# HSI-interface-2.net
KiCad netlist of a schematic drawn in EAGLE
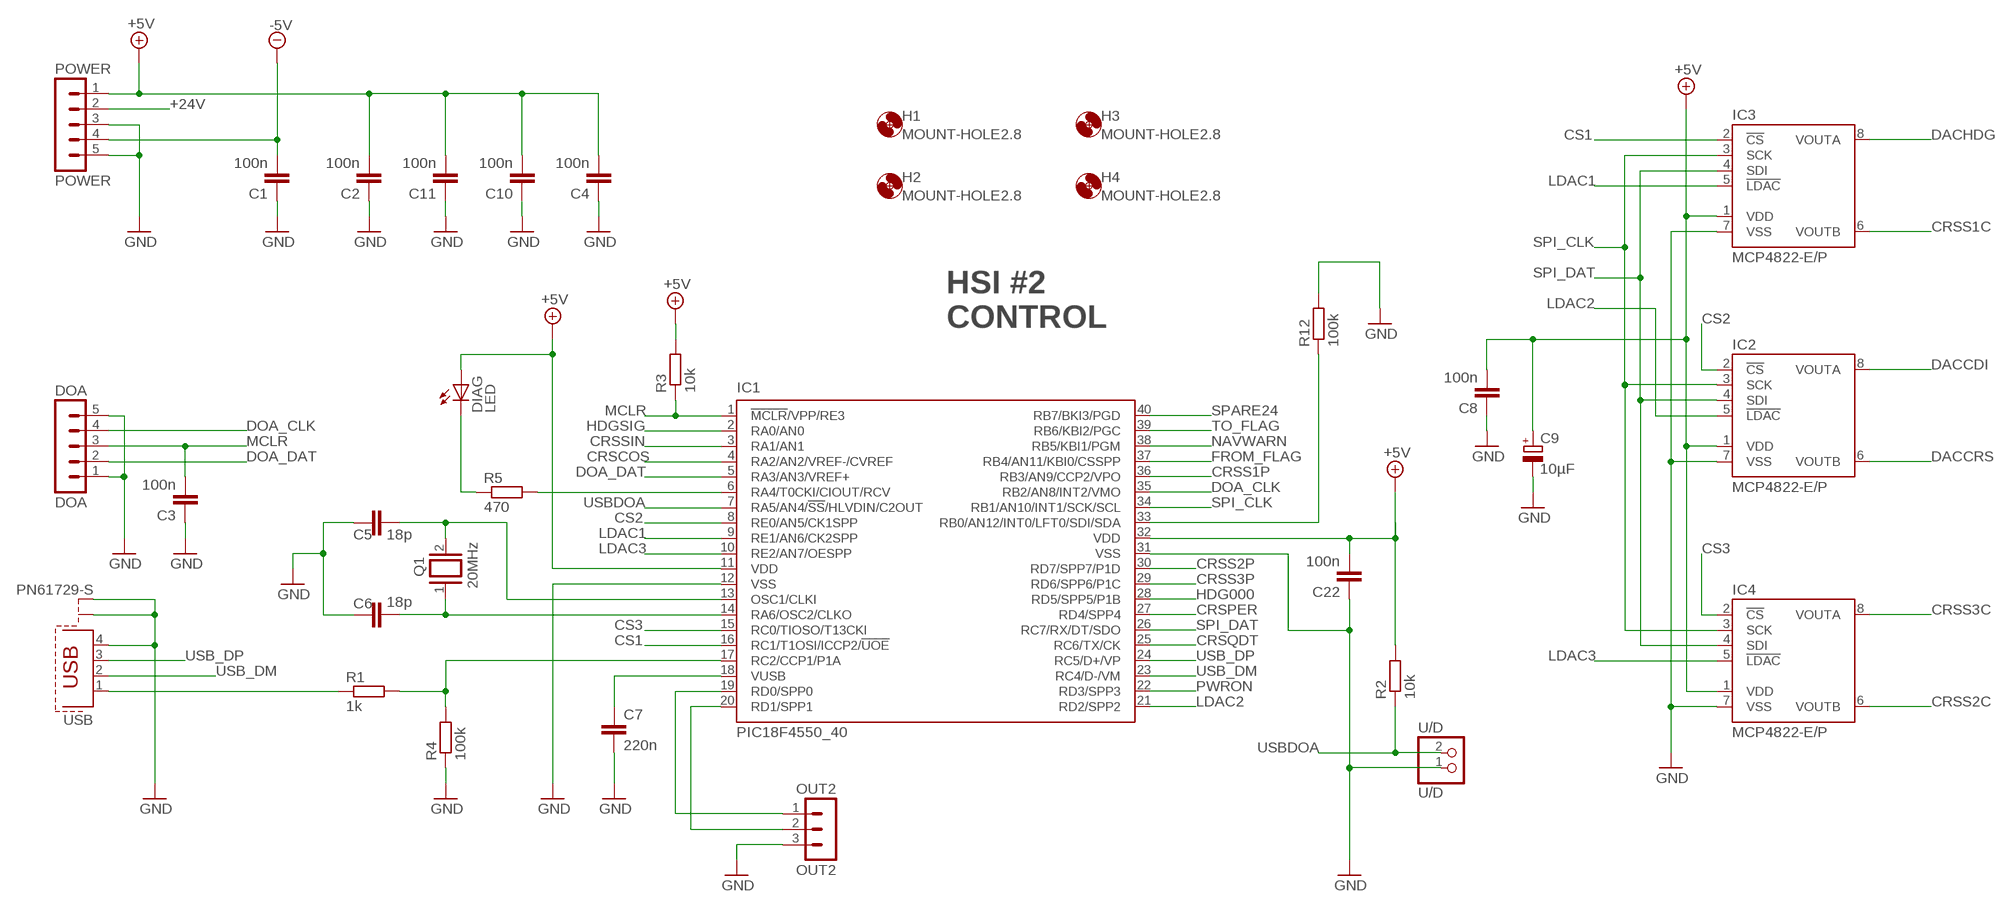
[diagram p0: schematic, sheet 1]
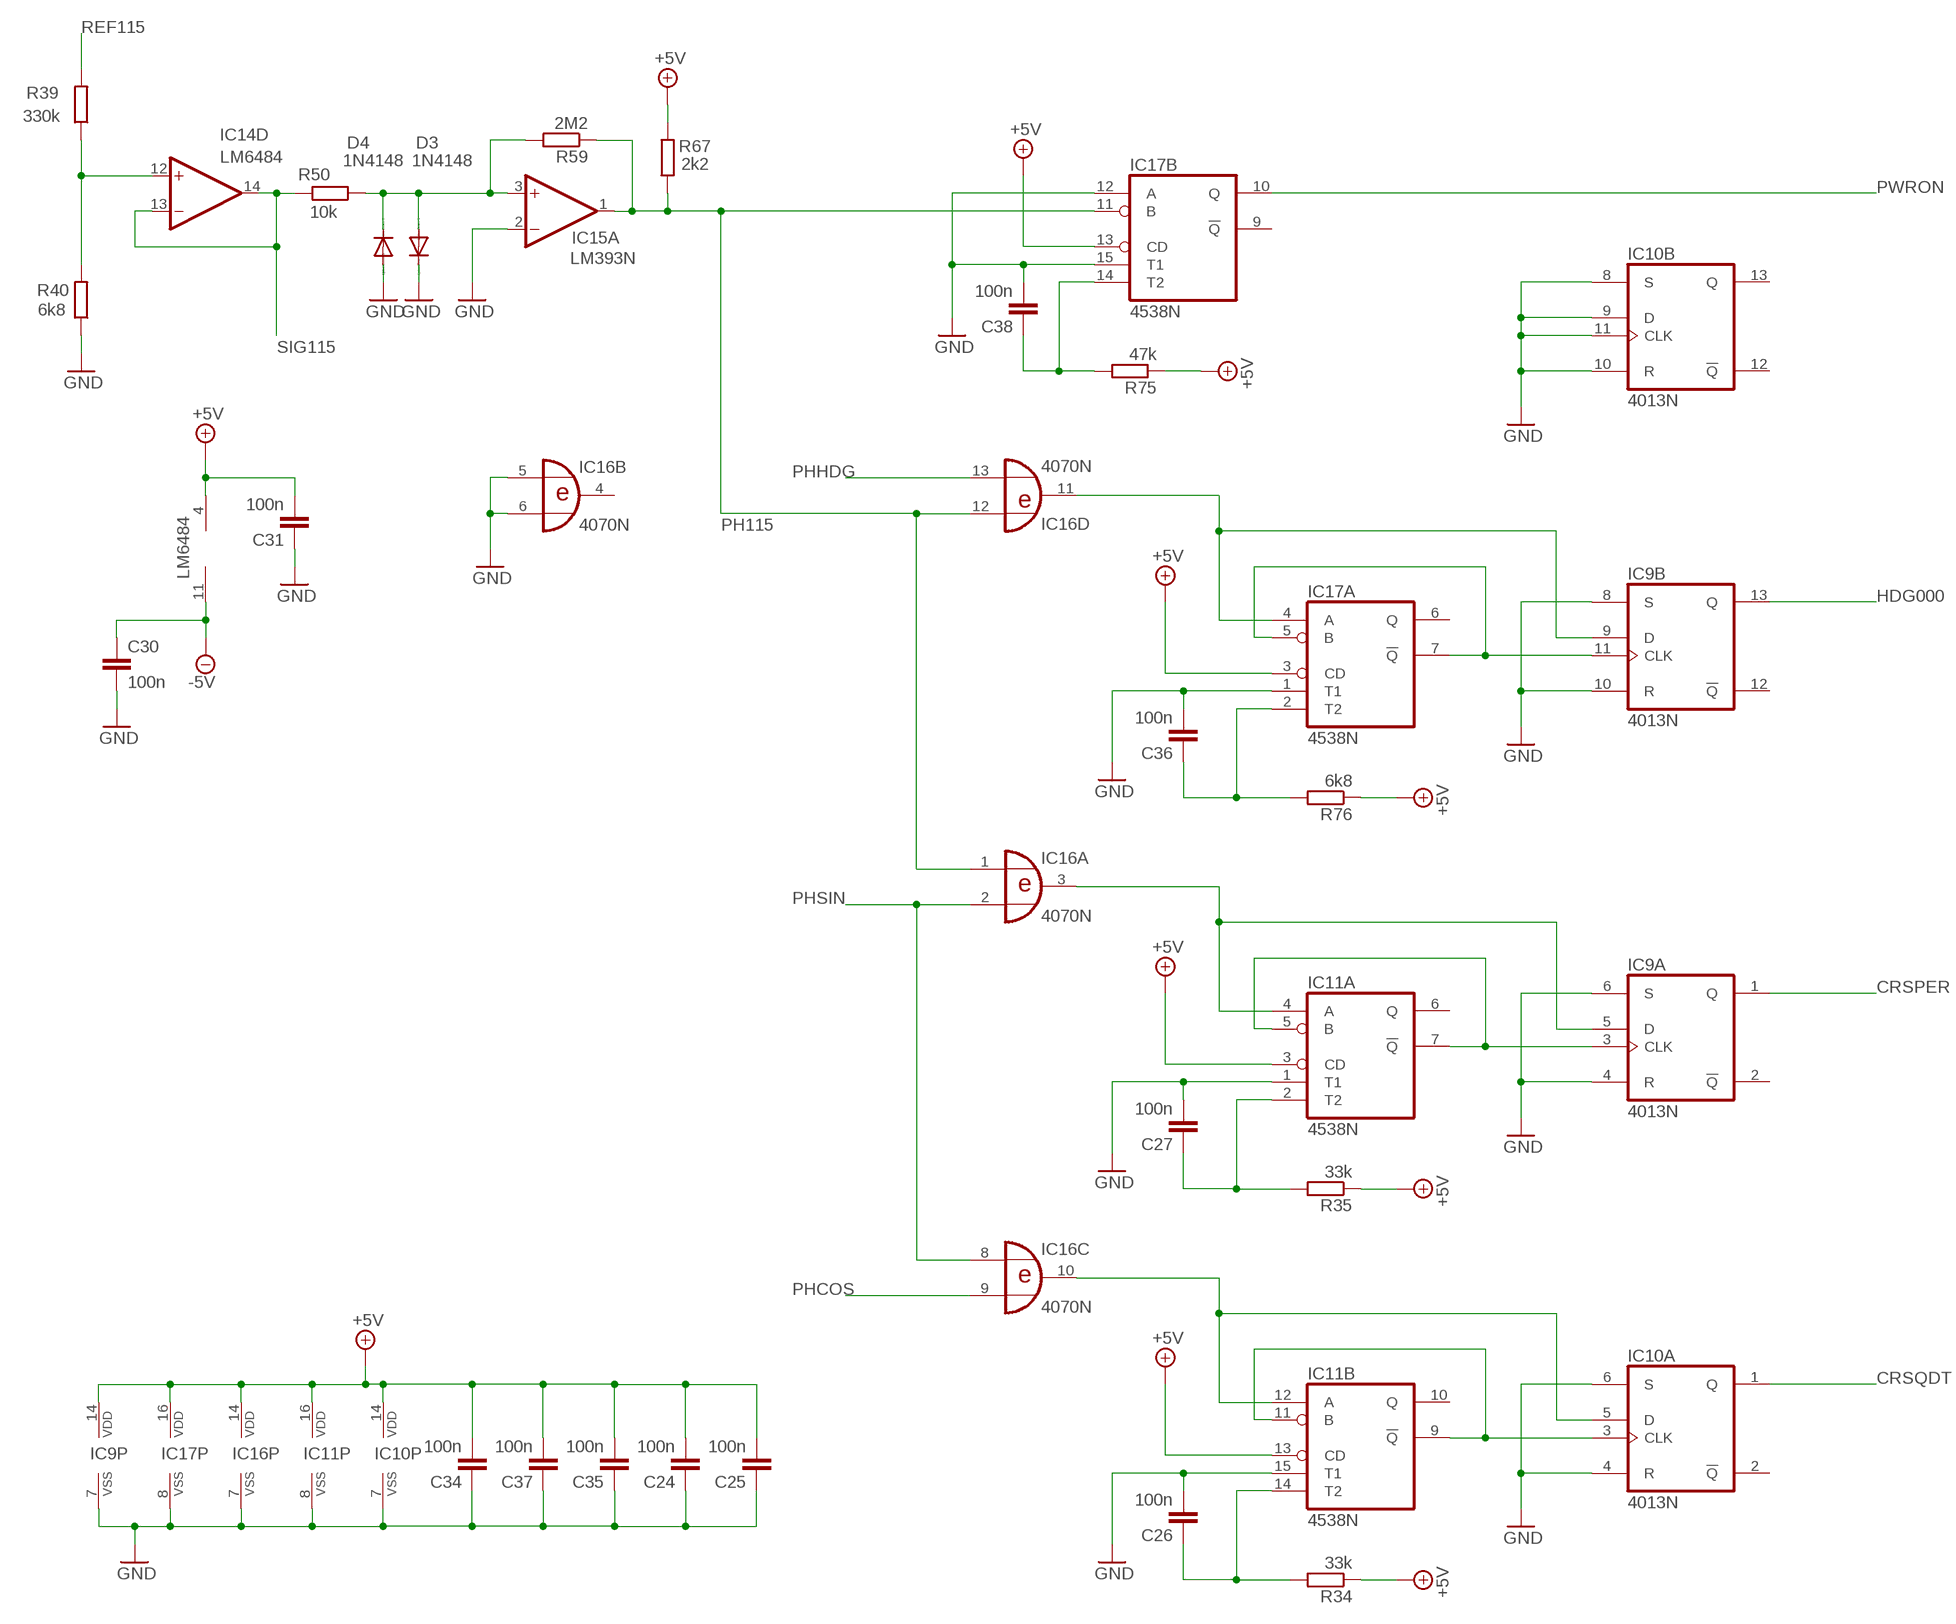
[diagram p1: schematic, sheet 2]
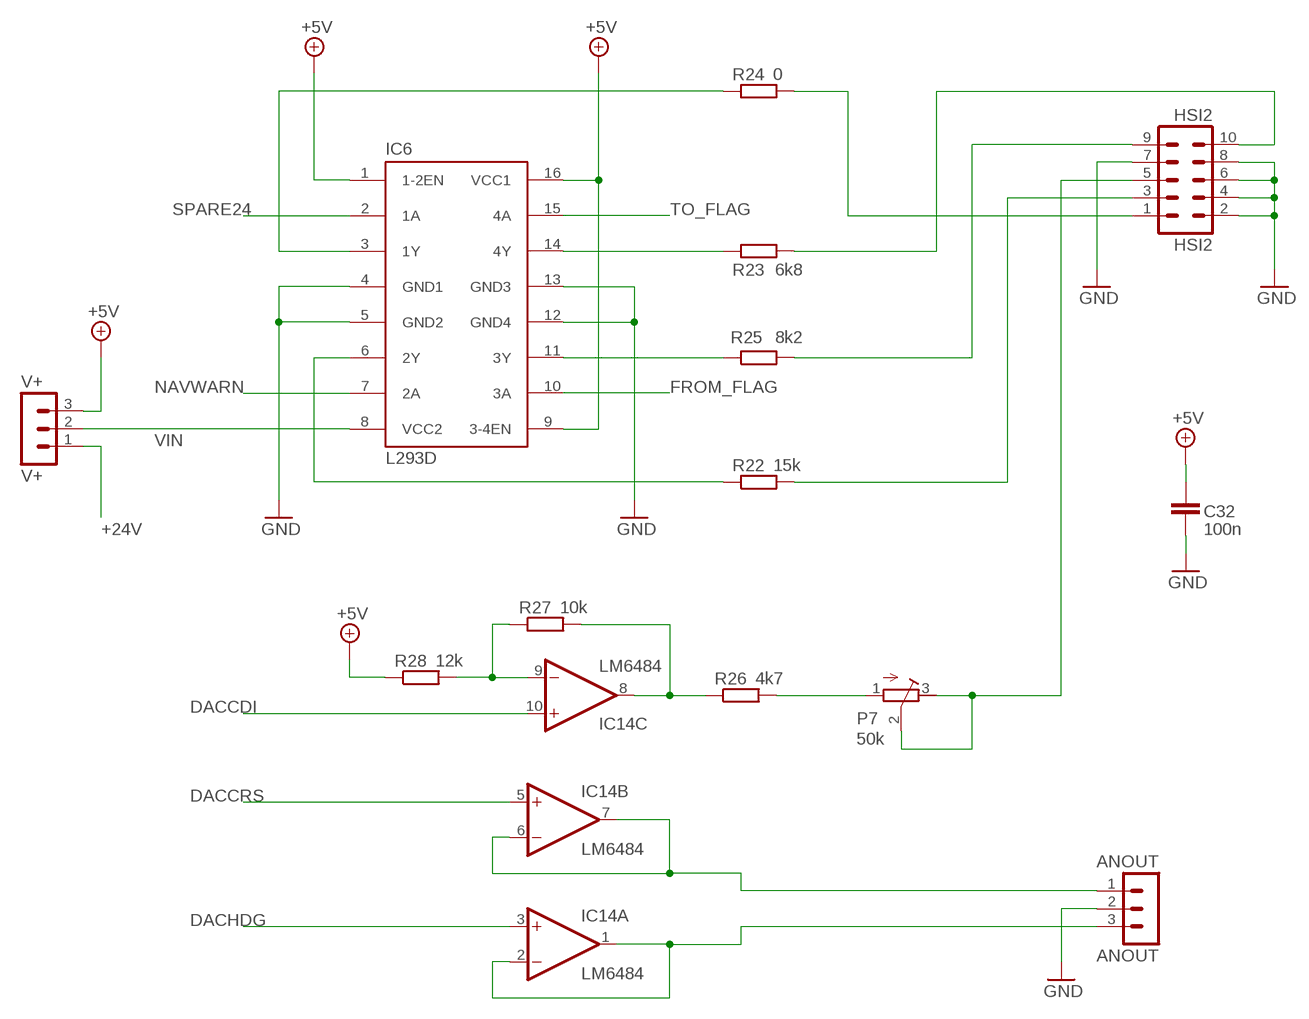
[diagram p2: schematic, sheet 3]
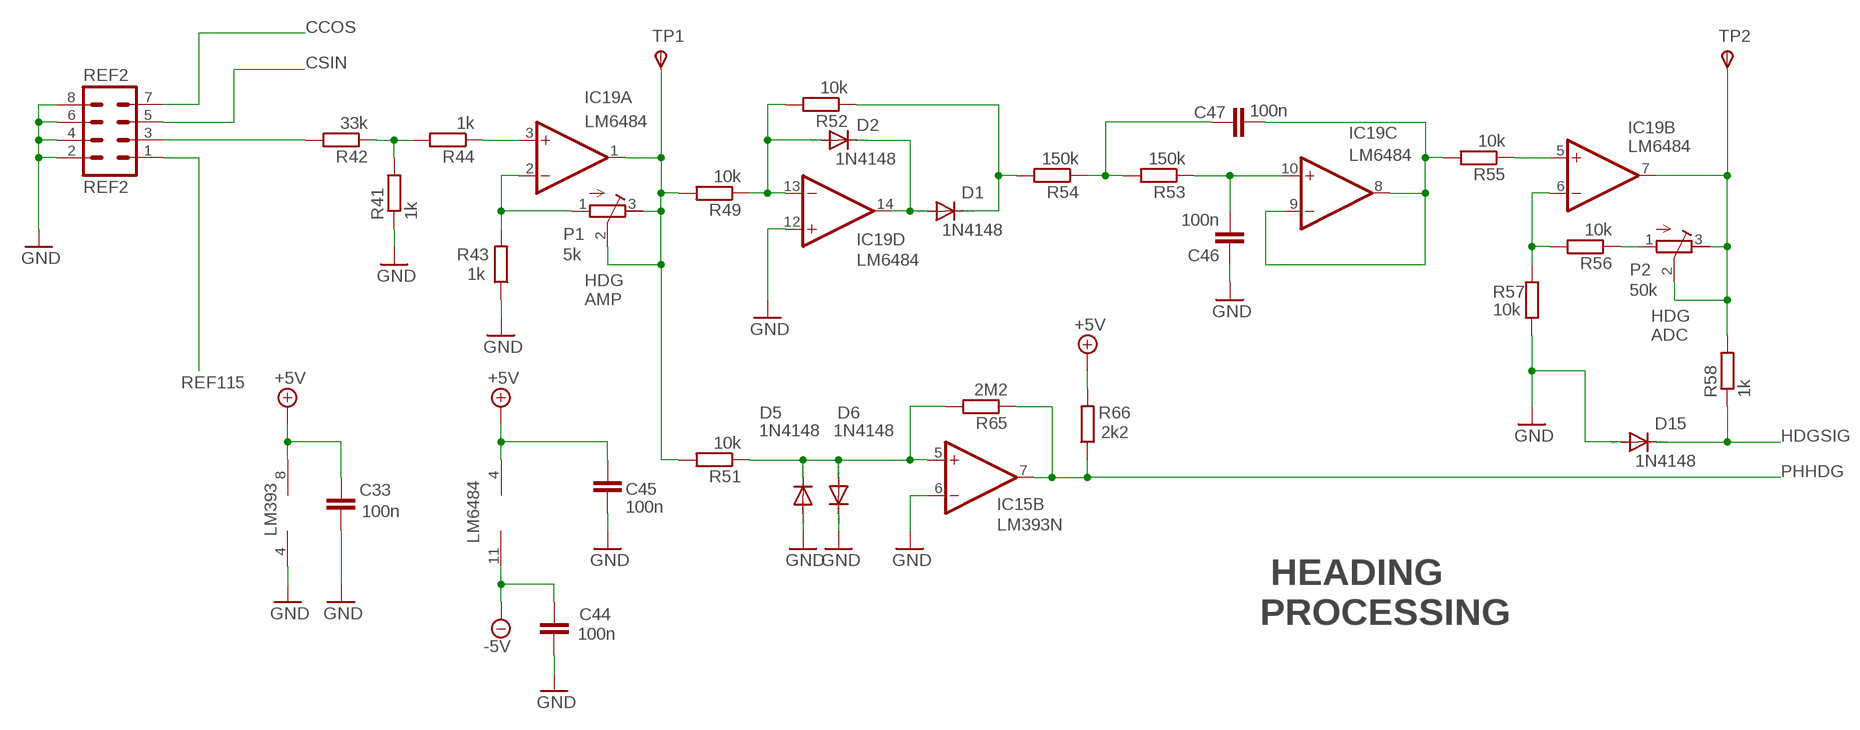
[diagram p3: schematic, sheet 4]
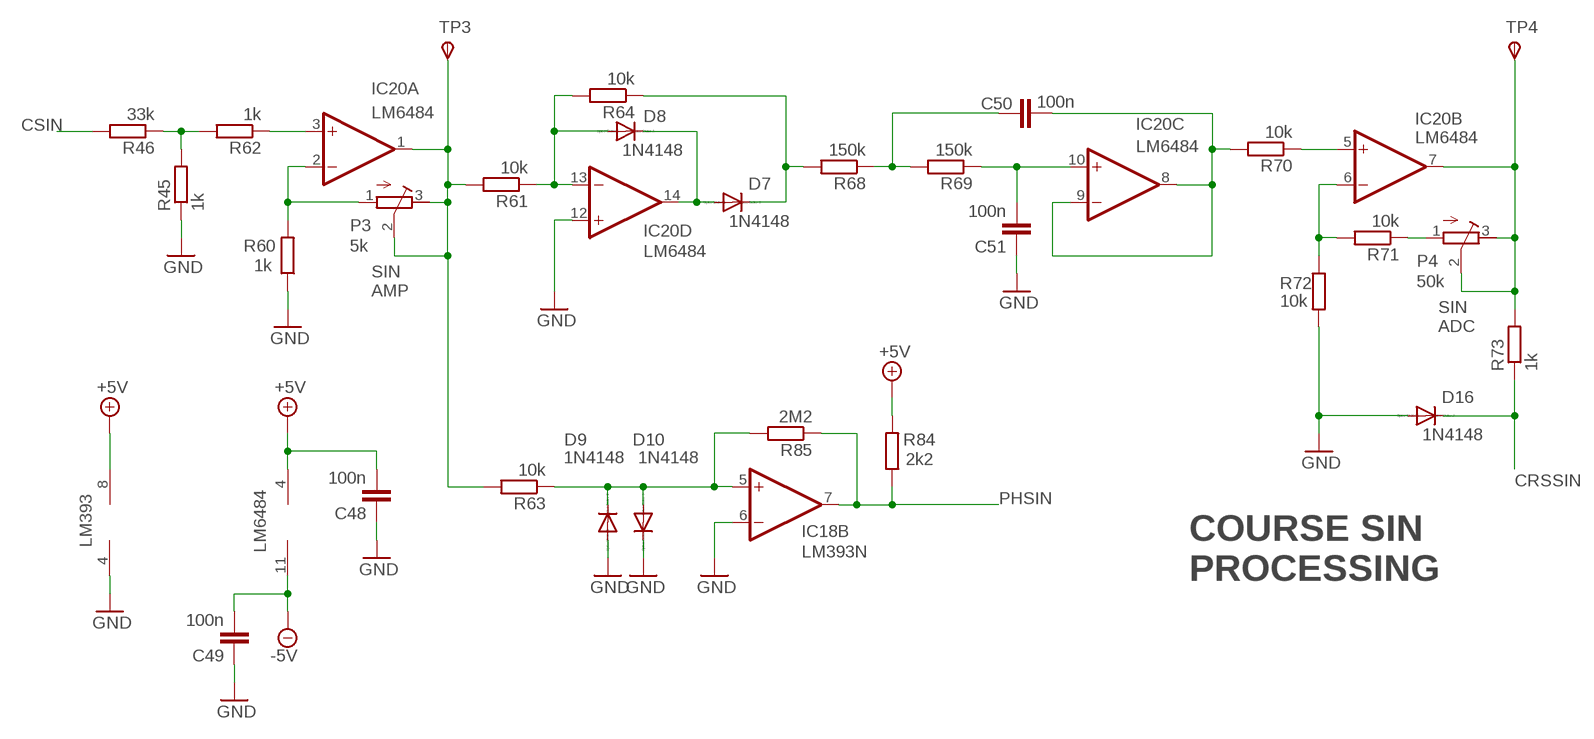
[diagram p4: schematic, sheet 5]
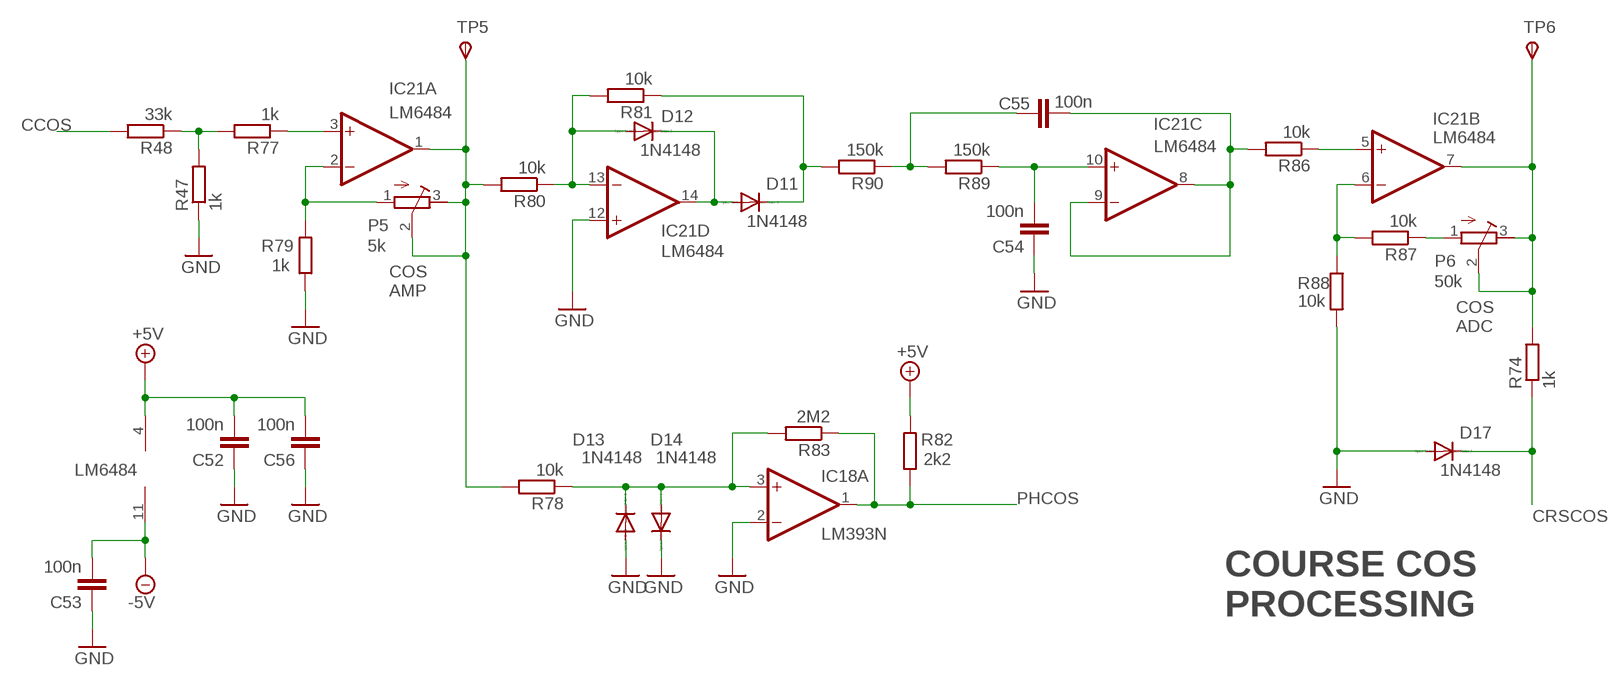
[diagram p5: schematic, sheet 6]
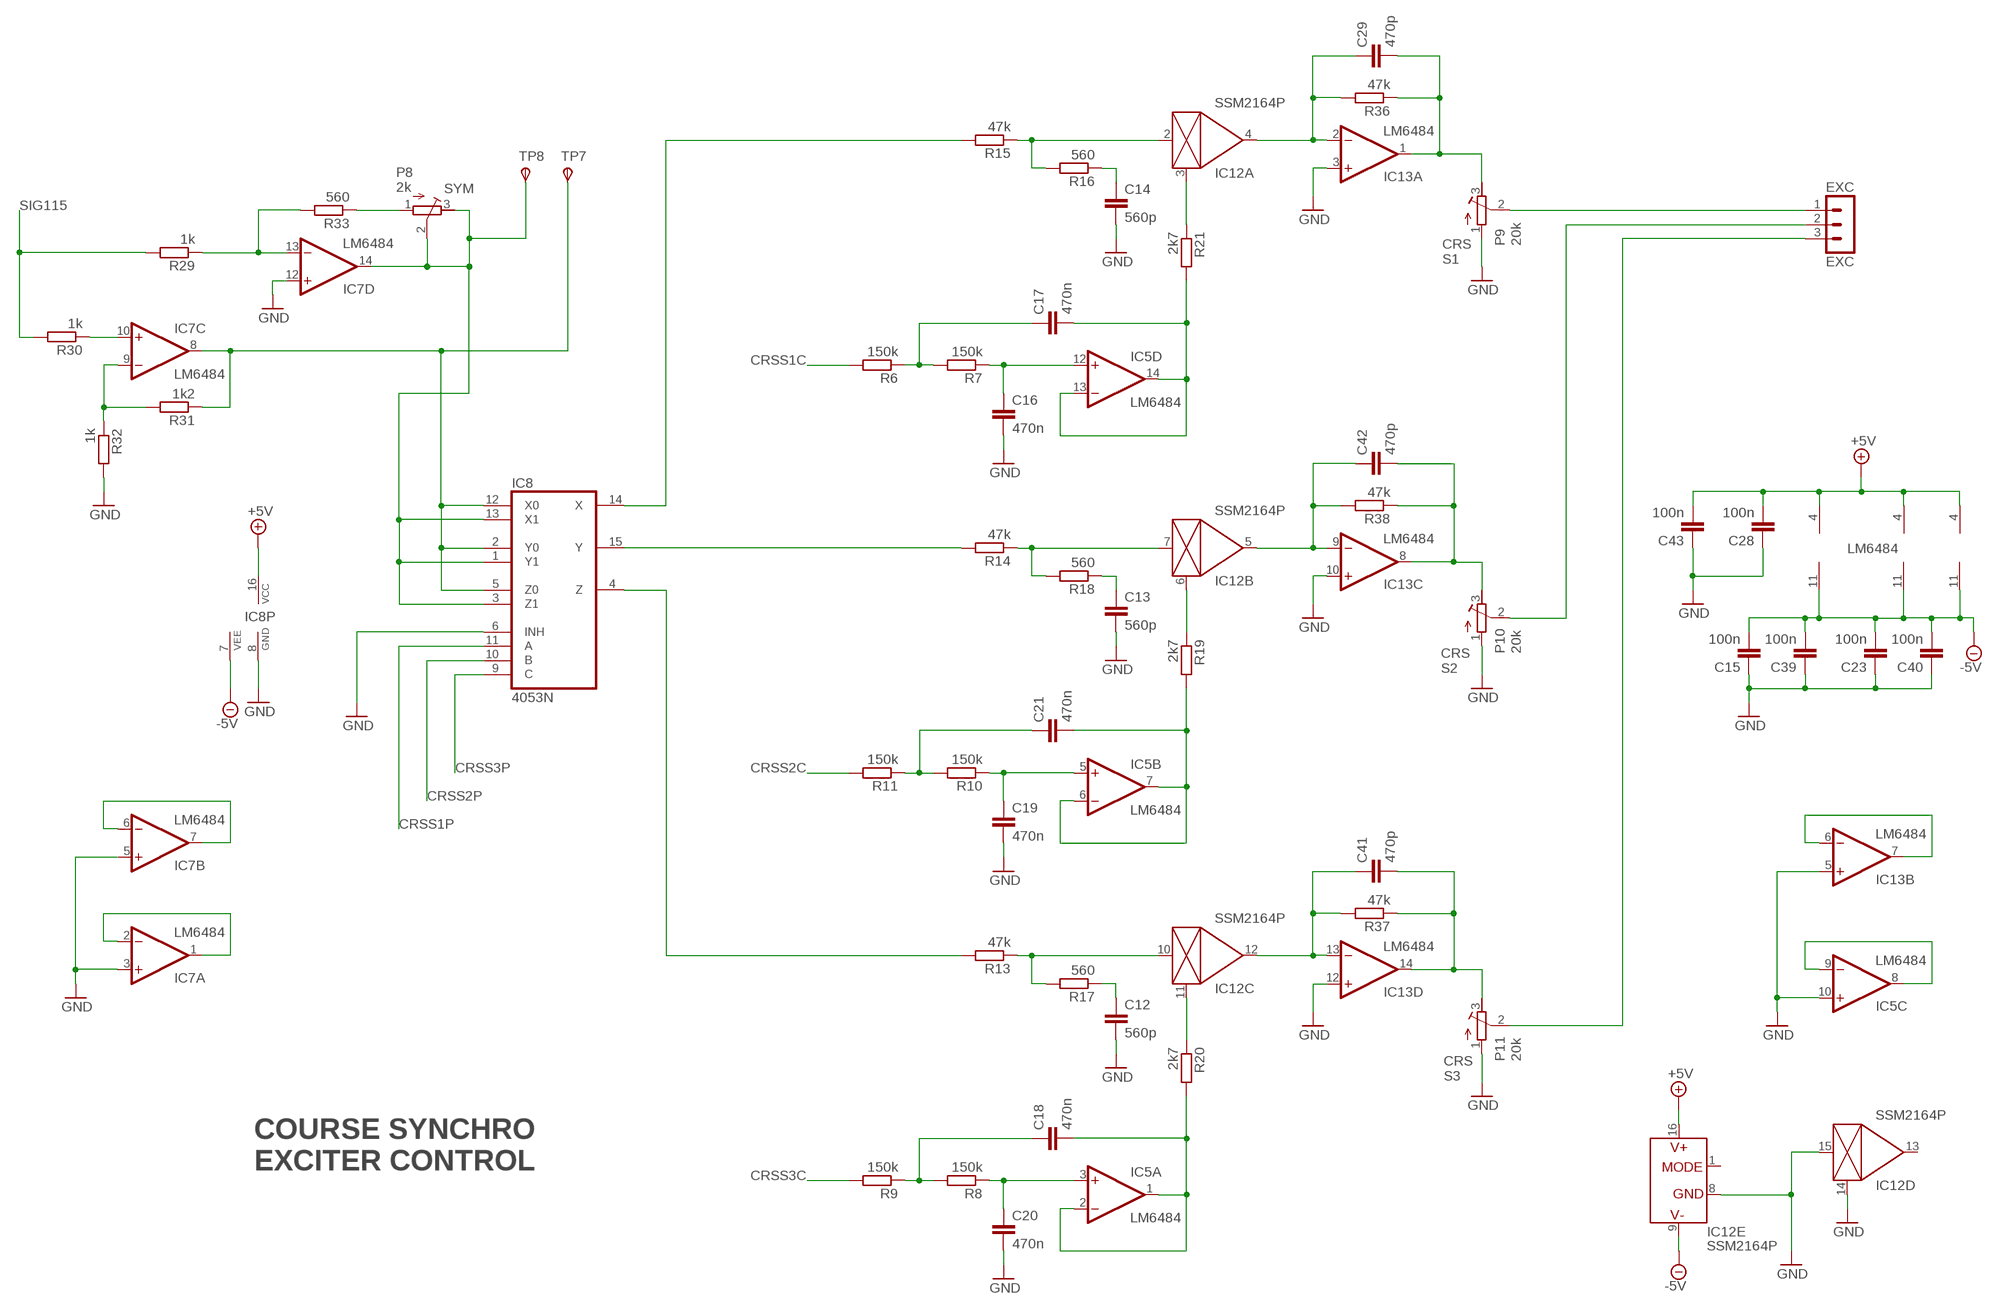
[diagram p6: schematic, sheet 7]

(export (version "E")
  (design (tool "Eeschema 10.0.6"))
  (components
    (comp (ref "C33")
      (value "100n")
      (footprint "eagle-import:C025-025X050")
      (libsource (lib "eagle-import") (part "C-EU025-025X050"))
    )
    (comp (ref "C44")
      (value "100n")
      (footprint "eagle-import:C025-025X050")
      (libsource (lib "eagle-import") (part "C-EU025-025X050"))
    )
    (comp (ref "C45")
      (value "100n")
      (footprint "eagle-import:C025-025X050")
      (libsource (lib "eagle-import") (part "C-EU025-025X050"))
    )
    (comp (ref "C46")
      (value "100n")
      (footprint "eagle-import:C025-025X050")
      (libsource (lib "eagle-import") (part "C-EU025-025X050"))
    )
    (comp (ref "C47")
      (value "100n")
      (footprint "eagle-import:C025-025X050")
      (libsource (lib "eagle-import") (part "C-EU025-025X050"))
    )
    (comp (ref "D1")
      (value "1N4148")
      (footprint "eagle-import:DO35-7")
      (libsource (lib "eagle-import") (part "1N4148DO35-7"))
    )
    (comp (ref "D2")
      (value "1N4148")
      (footprint "eagle-import:DO35-7")
      (libsource (lib "eagle-import") (part "1N4148DO35-7"))
    )
    (comp (ref "D5")
      (value "1N4148")
      (footprint "eagle-import:DO35-7")
      (libsource (lib "eagle-import") (part "1N4148DO35-7"))
    )
    (comp (ref "D6")
      (value "1N4148")
      (footprint "eagle-import:DO35-7")
      (libsource (lib "eagle-import") (part "1N4148DO35-7"))
    )
    (comp (ref "D15")
      (value "1N4148")
      (footprint "eagle-import:DO35-7")
      (libsource (lib "eagle-import") (part "1N4148DO35-7"))
    )
    (comp (ref "IC15")
      (value "LM393N")
      (footprint "eagle-import:DIL08")
      (libsource (lib "eagle-import") (part "LM393N"))
    )
    (comp (ref "IC19")
      (value "LM6484")
      (footprint "eagle-import:DIL14")
      (libsource (lib "eagle-import") (part "LM324N"))
    )
    (comp (ref "P1")
      (value "5k")
      (footprint "eagle-import:RTRIM64Z")
      (libsource (lib "eagle-import") (part "R-TRIMM64Z"))
    )
    (comp (ref "P2")
      (value "50k")
      (footprint "eagle-import:RTRIM64Z")
      (libsource (lib "eagle-import") (part "R-TRIMM64Z"))
    )
    (comp (ref "R41")
      (value "1k")
      (footprint "eagle-import:0204_7")
      (libsource (lib "eagle-import") (part "R-EU_0204/7"))
    )
    (comp (ref "R42")
      (value "33k")
      (footprint "eagle-import:0204_7")
      (libsource (lib "eagle-import") (part "R-EU_0204/7"))
    )
    (comp (ref "R43")
      (value "1k")
      (footprint "eagle-import:0204_7")
      (libsource (lib "eagle-import") (part "R-EU_0204/7"))
    )
    (comp (ref "R44")
      (value "1k")
      (footprint "eagle-import:0204_7")
      (libsource (lib "eagle-import") (part "R-EU_0204/7"))
    )
    (comp (ref "R49")
      (value "10k")
      (footprint "eagle-import:0204_7")
      (libsource (lib "eagle-import") (part "R-EU_0204/7"))
    )
    (comp (ref "R51")
      (value "10k")
      (footprint "eagle-import:0204_7")
      (libsource (lib "eagle-import") (part "R-EU_0204/7"))
    )
    (comp (ref "R52")
      (value "10k")
      (footprint "eagle-import:0204_7")
      (libsource (lib "eagle-import") (part "R-EU_0204/7"))
    )
    (comp (ref "R53")
      (value "150k")
      (footprint "eagle-import:0204_7")
      (libsource (lib "eagle-import") (part "R-EU_0204/7"))
    )
    (comp (ref "R54")
      (value "150k")
      (footprint "eagle-import:0204_7")
      (libsource (lib "eagle-import") (part "R-EU_0204/7"))
    )
    (comp (ref "R55")
      (value "10k")
      (footprint "eagle-import:0204_7")
      (libsource (lib "eagle-import") (part "R-EU_0204/7"))
    )
    (comp (ref "R56")
      (value "10k")
      (footprint "eagle-import:0204_7")
      (libsource (lib "eagle-import") (part "R-EU_0204/7"))
    )
    (comp (ref "R57")
      (value "10k")
      (footprint "eagle-import:0204_7")
      (libsource (lib "eagle-import") (part "R-EU_0204/7"))
    )
    (comp (ref "R58")
      (value "1k")
      (footprint "eagle-import:0204_7")
      (libsource (lib "eagle-import") (part "R-EU_0204/7"))
    )
    (comp (ref "R65")
      (value "2M2")
      (footprint "eagle-import:0204_7")
      (libsource (lib "eagle-import") (part "R-EU_0204/7"))
    )
    (comp (ref "R66")
      (value "2k2")
      (footprint "eagle-import:0204_7")
      (libsource (lib "eagle-import") (part "R-EU_0204/7"))
    )
    (comp (ref "REF2")
      (value "REF2")
      (footprint "eagle-import:MA04-2")
      (libsource (lib "eagle-import") (part "MA04-2"))
    )
    (comp (ref "TP1")
      (value "TPSPAD1-13")
      (footprint "eagle-import:P1-13")
      (libsource (lib "eagle-import") (part "TPSPAD1-13"))
    )
    (comp (ref "TP2")
      (value "TPSPAD1-13")
      (footprint "eagle-import:P1-13")
      (libsource (lib "eagle-import") (part "TPSPAD1-13"))
    )
    (comp (ref "C1")
      (value "100n")
      (footprint "eagle-import:C025-025X050")
      (libsource (lib "eagle-import") (part "C-EU025-025X050"))
    )
    (comp (ref "C2")
      (value "100n")
      (footprint "eagle-import:C025-025X050")
      (libsource (lib "eagle-import") (part "C-EU025-025X050"))
    )
    (comp (ref "C3")
      (value "100n")
      (footprint "eagle-import:C025-025X050")
      (libsource (lib "eagle-import") (part "C-EU025-025X050"))
    )
    (comp (ref "C4")
      (value "100n")
      (footprint "eagle-import:C025-025X050")
      (libsource (lib "eagle-import") (part "C-EU025-025X050"))
    )
    (comp (ref "C5")
      (value "18p")
      (footprint "eagle-import:C025-025X050")
      (libsource (lib "eagle-import") (part "C-EU025-025X050"))
    )
    (comp (ref "C6")
      (value "18p")
      (footprint "eagle-import:C025-025X050")
      (libsource (lib "eagle-import") (part "C-EU025-025X050"))
    )
    (comp (ref "C7")
      (value "220n")
      (footprint "eagle-import:C5B3")
      (libsource (lib "eagle-import") (part "C5/3"))
    )
    (comp (ref "C8")
      (value "100n")
      (footprint "eagle-import:C025-025X050")
      (libsource (lib "eagle-import") (part "C-EU025-025X050"))
    )
    (comp (ref "C9")
      (value "10µF")
      (footprint "eagle-import:E2,5-5")
      (libsource (lib "eagle-import") (part "CPOL-EUE2.5-5"))
    )
    (comp (ref "C10")
      (value "100n")
      (footprint "eagle-import:C025-025X050")
      (libsource (lib "eagle-import") (part "C-EU025-025X050"))
    )
    (comp (ref "C11")
      (value "100n")
      (footprint "eagle-import:C025-025X050")
      (libsource (lib "eagle-import") (part "C-EU025-025X050"))
    )
    (comp (ref "C22")
      (value "100n")
      (footprint "eagle-import:C025-025X050")
      (libsource (lib "eagle-import") (part "C-EU025-025X050"))
    )
    (comp (ref "DIAG")
      (value "LED")
      (footprint "eagle-import:LED3MM")
      (libsource (lib "eagle-import") (part "LED3MM"))
    )
    (comp (ref "DOA")
      (value "DOA")
      (footprint "eagle-import:MA05-1")
      (libsource (lib "eagle-import") (part "MA05-1"))
    )
    (comp (ref "H1")
      (value "MOUNT-HOLE2.8")
      (footprint "eagle-import:2,8")
      (libsource (lib "eagle-import") (part "MOUNT-HOLE2.8"))
    )
    (comp (ref "H2")
      (value "MOUNT-HOLE2.8")
      (footprint "eagle-import:2,8")
      (libsource (lib "eagle-import") (part "MOUNT-HOLE2.8"))
    )
    (comp (ref "H3")
      (value "MOUNT-HOLE2.8")
      (footprint "eagle-import:2,8")
      (libsource (lib "eagle-import") (part "MOUNT-HOLE2.8"))
    )
    (comp (ref "H4")
      (value "MOUNT-HOLE2.8")
      (footprint "eagle-import:2,8")
      (libsource (lib "eagle-import") (part "MOUNT-HOLE2.8"))
    )
    (comp (ref "IC1")
      (value "PIC18F4550_40")
      (footprint "eagle-import:DIL40")
      (fields (field (name "MF") "MICROCHIP") (field (name "MPN") "PIC18F4550-I/P"))
      (libsource (lib "eagle-import") (part "PIC18F4_40550"))
    )
    (comp (ref "IC2")
      (value "MCP4822-E/P")
      (footprint "eagle-import:DIL08")
      (libsource (lib "eagle-import") (part "MCP4822-E/P"))
    )
    (comp (ref "IC3")
      (value "MCP4822-E/P")
      (footprint "eagle-import:DIL08")
      (libsource (lib "eagle-import") (part "MCP4822-E/P"))
    )
    (comp (ref "IC4")
      (value "MCP4822-E/P")
      (footprint "eagle-import:DIL08")
      (libsource (lib "eagle-import") (part "MCP4822-E/P"))
    )
    (comp (ref "OUT2")
      (value "OUT2")
      (footprint "eagle-import:MA03-1")
      (libsource (lib "eagle-import") (part "MA03-1"))
    )
    (comp (ref "POWER")
      (value "POWER")
      (footprint "eagle-import:MA05-1")
      (libsource (lib "eagle-import") (part "MA05-1"))
    )
    (comp (ref "Q1")
      (value "20MHz")
      (footprint "eagle-import:QS")
      (libsource (lib "eagle-import") (part "XTAL/S"))
    )
    (comp (ref "R1")
      (value "1k")
      (footprint "eagle-import:0204_7")
      (libsource (lib "eagle-import") (part "R-EU_0204/7"))
    )
    (comp (ref "R2")
      (value "10k")
      (footprint "eagle-import:0204_7")
      (libsource (lib "eagle-import") (part "R-EU_0204/7"))
    )
    (comp (ref "R3")
      (value "10k")
      (footprint "eagle-import:0204_7")
      (libsource (lib "eagle-import") (part "R-EU_0204/7"))
    )
    (comp (ref "R4")
      (value "100k")
      (footprint "eagle-import:0204_7")
      (libsource (lib "eagle-import") (part "R-EU_0204/7"))
    )
    (comp (ref "R5")
      (value "470")
      (footprint "eagle-import:0204_7")
      (libsource (lib "eagle-import") (part "R-EU_0204/7"))
    )
    (comp (ref "R12")
      (value "100k")
      (footprint "eagle-import:0204_7")
      (libsource (lib "eagle-import") (part "R-EU_0204/7"))
    )
    (comp (ref "U/D")
      (value "U/D")
      (footprint "eagle-import:1X02")
      (libsource (lib "eagle-import") (part "PINHD-1X2"))
    )
    (comp (ref "USB")
      (value "PN61729-S")
      (footprint "eagle-import:PN61729-S")
      (libsource (lib "eagle-import") (part "PN61729-S"))
    )
    (comp (ref "ANOUT")
      (value "ANOUT")
      (footprint "eagle-import:MA03-1")
      (libsource (lib "eagle-import") (part "MA03-1"))
    )
    (comp (ref "C32")
      (value "100n")
      (footprint "eagle-import:C025-025X050")
      (libsource (lib "eagle-import") (part "C-EU025-025X050"))
    )
    (comp (ref "HSI2")
      (value "HSI2")
      (footprint "eagle-import:MA05-2")
      (libsource (lib "eagle-import") (part "MA05-2"))
    )
    (comp (ref "IC6")
      (value "L293D")
      (footprint "eagle-import:DIL16")
      (libsource (lib "eagle-import") (part "L293D"))
    )
    (comp (ref "IC14")
      (value "LM6484")
      (footprint "eagle-import:DIL14")
      (libsource (lib "eagle-import") (part "LM324N"))
    )
    (comp (ref "P7")
      (value "50k")
      (footprint "eagle-import:RTRIM64Z")
      (libsource (lib "eagle-import") (part "R-TRIMM64Z"))
    )
    (comp (ref "R22")
      (value "15k")
      (footprint "eagle-import:0204_7")
      (libsource (lib "eagle-import") (part "R-EU_0204/7"))
    )
    (comp (ref "R23")
      (value "6k8")
      (footprint "eagle-import:0204_7")
      (libsource (lib "eagle-import") (part "R-EU_0204/7"))
    )
    (comp (ref "R24")
      (value "0")
      (footprint "eagle-import:0204_7")
      (libsource (lib "eagle-import") (part "R-EU_0204/7"))
    )
    (comp (ref "R25")
      (value "8k2")
      (footprint "eagle-import:0204_7")
      (libsource (lib "eagle-import") (part "R-EU_0204/7"))
    )
    (comp (ref "R26")
      (value "4k7")
      (footprint "eagle-import:0204_7")
      (libsource (lib "eagle-import") (part "R-EU_0204/7"))
    )
    (comp (ref "R27")
      (value "10k")
      (footprint "eagle-import:0204_7")
      (libsource (lib "eagle-import") (part "R-EU_0204/7"))
    )
    (comp (ref "R28")
      (value "12k")
      (footprint "eagle-import:0204_7")
      (libsource (lib "eagle-import") (part "R-EU_0204/7"))
    )
    (comp (ref "V+")
      (value "V+")
      (footprint "eagle-import:MA03-1")
      (libsource (lib "eagle-import") (part "MA03-1"))
    )
    (comp (ref "C24")
      (value "100n")
      (footprint "eagle-import:C025-025X050")
      (libsource (lib "eagle-import") (part "C-EU025-025X050"))
    )
    (comp (ref "C25")
      (value "100n")
      (footprint "eagle-import:C025-025X050")
      (libsource (lib "eagle-import") (part "C-EU025-025X050"))
    )
    (comp (ref "C26")
      (value "100n")
      (footprint "eagle-import:C025-025X050")
      (libsource (lib "eagle-import") (part "C-EU025-025X050"))
    )
    (comp (ref "C27")
      (value "100n")
      (footprint "eagle-import:C025-025X050")
      (libsource (lib "eagle-import") (part "C-EU025-025X050"))
    )
    (comp (ref "C30")
      (value "100n")
      (footprint "eagle-import:C025-025X050")
      (libsource (lib "eagle-import") (part "C-EU025-025X050"))
    )
    (comp (ref "C31")
      (value "100n")
      (footprint "eagle-import:C025-025X050")
      (libsource (lib "eagle-import") (part "C-EU025-025X050"))
    )
    (comp (ref "C34")
      (value "100n")
      (footprint "eagle-import:C025-025X050")
      (libsource (lib "eagle-import") (part "C-EU025-025X050"))
    )
    (comp (ref "C35")
      (value "100n")
      (footprint "eagle-import:C025-025X050")
      (libsource (lib "eagle-import") (part "C-EU025-025X050"))
    )
    (comp (ref "C36")
      (value "100n")
      (footprint "eagle-import:C025-025X050")
      (libsource (lib "eagle-import") (part "C-EU025-025X050"))
    )
    (comp (ref "C37")
      (value "100n")
      (footprint "eagle-import:C025-025X050")
      (libsource (lib "eagle-import") (part "C-EU025-025X050"))
    )
    (comp (ref "C38")
      (value "100n")
      (footprint "eagle-import:C025-025X050")
      (libsource (lib "eagle-import") (part "C-EU025-025X050"))
    )
    (comp (ref "D3")
      (value "1N4148")
      (footprint "eagle-import:DO35-7")
      (libsource (lib "eagle-import") (part "1N4148DO35-7"))
    )
    (comp (ref "D4")
      (value "1N4148")
      (footprint "eagle-import:DO35-7")
      (libsource (lib "eagle-import") (part "1N4148DO35-7"))
    )
    (comp (ref "IC9")
      (value "4013N")
      (footprint "eagle-import:DIL14")
      (libsource (lib "eagle-import") (part "4013N"))
    )
    (comp (ref "IC10")
      (value "4013N")
      (footprint "eagle-import:DIL14")
      (libsource (lib "eagle-import") (part "4013N"))
    )
    (comp (ref "IC11")
      (value "4538N")
      (footprint "eagle-import:DIL16")
      (libsource (lib "eagle-import") (part "4538N"))
    )
    (comp (ref "IC16")
      (value "4070N")
      (footprint "eagle-import:DIL14")
      (libsource (lib "eagle-import") (part "4070N"))
    )
    (comp (ref "IC17")
      (value "4538N")
      (footprint "eagle-import:DIL16")
      (libsource (lib "eagle-import") (part "4538N"))
    )
    (comp (ref "R34")
      (value "33k")
      (footprint "eagle-import:0204_7")
      (libsource (lib "eagle-import") (part "R-EU_0204/7"))
    )
    (comp (ref "R35")
      (value "33k")
      (footprint "eagle-import:0204_7")
      (libsource (lib "eagle-import") (part "R-EU_0204/7"))
    )
    (comp (ref "R39")
      (value "330k")
      (footprint "eagle-import:0204_7")
      (libsource (lib "eagle-import") (part "R-EU_0204/7"))
    )
    (comp (ref "R40")
      (value "6k8")
      (footprint "eagle-import:0204_7")
      (libsource (lib "eagle-import") (part "R-EU_0204/7"))
    )
    (comp (ref "R50")
      (value "10k")
      (footprint "eagle-import:0204_7")
      (libsource (lib "eagle-import") (part "R-EU_0204/7"))
    )
    (comp (ref "R59")
      (value "2M2")
      (footprint "eagle-import:0204_7")
      (libsource (lib "eagle-import") (part "R-EU_0204/7"))
    )
    (comp (ref "R67")
      (value "2k2")
      (footprint "eagle-import:0204_7")
      (libsource (lib "eagle-import") (part "R-EU_0204/7"))
    )
    (comp (ref "R75")
      (value "47k")
      (footprint "eagle-import:0204_7")
      (libsource (lib "eagle-import") (part "R-EU_0204/7"))
    )
    (comp (ref "R76")
      (value "6k8")
      (footprint "eagle-import:0204_7")
      (libsource (lib "eagle-import") (part "R-EU_0204/7"))
    )
    (comp (ref "C48")
      (value "100n")
      (footprint "eagle-import:C025-025X050")
      (libsource (lib "eagle-import") (part "C-EU025-025X050"))
    )
    (comp (ref "C49")
      (value "100n")
      (footprint "eagle-import:C025-025X050")
      (libsource (lib "eagle-import") (part "C-EU025-025X050"))
    )
    (comp (ref "C50")
      (value "100n")
      (footprint "eagle-import:C025-025X050")
      (libsource (lib "eagle-import") (part "C-EU025-025X050"))
    )
    (comp (ref "C51")
      (value "100n")
      (footprint "eagle-import:C025-025X050")
      (libsource (lib "eagle-import") (part "C-EU025-025X050"))
    )
    (comp (ref "D7")
      (value "1N4148")
      (footprint "eagle-import:DO35-7")
      (libsource (lib "eagle-import") (part "1N4148DO35-7"))
    )
    (comp (ref "D8")
      (value "1N4148")
      (footprint "eagle-import:DO35-7")
      (libsource (lib "eagle-import") (part "1N4148DO35-7"))
    )
    (comp (ref "D9")
      (value "1N4148")
      (footprint "eagle-import:DO35-7")
      (libsource (lib "eagle-import") (part "1N4148DO35-7"))
    )
    (comp (ref "D10")
      (value "1N4148")
      (footprint "eagle-import:DO35-7")
      (libsource (lib "eagle-import") (part "1N4148DO35-7"))
    )
    (comp (ref "D16")
      (value "1N4148")
      (footprint "eagle-import:DO35-7")
      (libsource (lib "eagle-import") (part "1N4148DO35-7"))
    )
    (comp (ref "IC18")
      (value "LM393N")
      (footprint "eagle-import:DIL08")
      (libsource (lib "eagle-import") (part "LM393N"))
    )
    (comp (ref "IC20")
      (value "LM6484")
      (footprint "eagle-import:DIL14")
      (libsource (lib "eagle-import") (part "LM324N"))
    )
    (comp (ref "P3")
      (value "5k")
      (footprint "eagle-import:RTRIM64Z")
      (libsource (lib "eagle-import") (part "R-TRIMM64Z"))
    )
    (comp (ref "P4")
      (value "50k")
      (footprint "eagle-import:RTRIM64Z")
      (libsource (lib "eagle-import") (part "R-TRIMM64Z"))
    )
    (comp (ref "R45")
      (value "1k")
      (footprint "eagle-import:0204_7")
      (libsource (lib "eagle-import") (part "R-EU_0204/7"))
    )
    (comp (ref "R46")
      (value "33k")
      (footprint "eagle-import:0204_7")
      (libsource (lib "eagle-import") (part "R-EU_0204/7"))
    )
    (comp (ref "R60")
      (value "1k")
      (footprint "eagle-import:0204_7")
      (libsource (lib "eagle-import") (part "R-EU_0204/7"))
    )
    (comp (ref "R61")
      (value "10k")
      (footprint "eagle-import:0204_7")
      (libsource (lib "eagle-import") (part "R-EU_0204/7"))
    )
    (comp (ref "R62")
      (value "1k")
      (footprint "eagle-import:0204_7")
      (libsource (lib "eagle-import") (part "R-EU_0204/7"))
    )
    (comp (ref "R63")
      (value "10k")
      (footprint "eagle-import:0204_7")
      (libsource (lib "eagle-import") (part "R-EU_0204/7"))
    )
    (comp (ref "R64")
      (value "10k")
      (footprint "eagle-import:0204_7")
      (libsource (lib "eagle-import") (part "R-EU_0204/7"))
    )
    (comp (ref "R68")
      (value "150k")
      (footprint "eagle-import:0204_7")
      (libsource (lib "eagle-import") (part "R-EU_0204/7"))
    )
    (comp (ref "R69")
      (value "150k")
      (footprint "eagle-import:0204_7")
      (libsource (lib "eagle-import") (part "R-EU_0204/7"))
    )
    (comp (ref "R70")
      (value "10k")
      (footprint "eagle-import:0204_7")
      (libsource (lib "eagle-import") (part "R-EU_0204/7"))
    )
    (comp (ref "R71")
      (value "10k")
      (footprint "eagle-import:0204_7")
      (libsource (lib "eagle-import") (part "R-EU_0204/7"))
    )
    (comp (ref "R72")
      (value "10k")
      (footprint "eagle-import:0204_7")
      (libsource (lib "eagle-import") (part "R-EU_0204/7"))
    )
    (comp (ref "R73")
      (value "1k")
      (footprint "eagle-import:0204_7")
      (libsource (lib "eagle-import") (part "R-EU_0204/7"))
    )
    (comp (ref "R84")
      (value "2k2")
      (footprint "eagle-import:0204_7")
      (libsource (lib "eagle-import") (part "R-EU_0204/7"))
    )
    (comp (ref "R85")
      (value "2M2")
      (footprint "eagle-import:0204_7")
      (libsource (lib "eagle-import") (part "R-EU_0204/7"))
    )
    (comp (ref "TP3")
      (value "TPSPAD1-13")
      (footprint "eagle-import:P1-13")
      (libsource (lib "eagle-import") (part "TPSPAD1-13"))
    )
    (comp (ref "TP4")
      (value "TPSPAD1-13")
      (footprint "eagle-import:P1-13")
      (libsource (lib "eagle-import") (part "TPSPAD1-13"))
    )
    (comp (ref "C12")
      (value "560p")
      (footprint "eagle-import:C025-025X050")
      (libsource (lib "eagle-import") (part "C-EU025-025X050"))
    )
    (comp (ref "C13")
      (value "560p")
      (footprint "eagle-import:C025-025X050")
      (libsource (lib "eagle-import") (part "C-EU025-025X050"))
    )
    (comp (ref "C14")
      (value "560p")
      (footprint "eagle-import:C025-025X050")
      (libsource (lib "eagle-import") (part "C-EU025-025X050"))
    )
    (comp (ref "C15")
      (value "100n")
      (footprint "eagle-import:C025-025X050")
      (libsource (lib "eagle-import") (part "C-EU025-025X050"))
    )
    (comp (ref "C16")
      (value "470n")
      (footprint "eagle-import:C025-025X050")
      (libsource (lib "eagle-import") (part "C-EU025-025X050"))
    )
    (comp (ref "C17")
      (value "470n")
      (footprint "eagle-import:C025-025X050")
      (libsource (lib "eagle-import") (part "C-EU025-025X050"))
    )
    (comp (ref "C18")
      (value "470n")
      (footprint "eagle-import:C025-025X050")
      (libsource (lib "eagle-import") (part "C-EU025-025X050"))
    )
    (comp (ref "C19")
      (value "470n")
      (footprint "eagle-import:C025-025X050")
      (libsource (lib "eagle-import") (part "C-EU025-025X050"))
    )
    (comp (ref "C20")
      (value "470n")
      (footprint "eagle-import:C025-025X050")
      (libsource (lib "eagle-import") (part "C-EU025-025X050"))
    )
    (comp (ref "C21")
      (value "470n")
      (footprint "eagle-import:C025-025X050")
      (libsource (lib "eagle-import") (part "C-EU025-025X050"))
    )
    (comp (ref "C23")
      (value "100n")
      (footprint "eagle-import:C025-025X050")
      (libsource (lib "eagle-import") (part "C-EU025-025X050"))
    )
    (comp (ref "C28")
      (value "100n")
      (footprint "eagle-import:C025-025X050")
      (libsource (lib "eagle-import") (part "C-EU025-025X050"))
    )
    (comp (ref "C29")
      (value "470p")
      (footprint "eagle-import:C025-025X050")
      (libsource (lib "eagle-import") (part "C-EU025-025X050"))
    )
    (comp (ref "C39")
      (value "100n")
      (footprint "eagle-import:C025-025X050")
      (libsource (lib "eagle-import") (part "C-EU025-025X050"))
    )
    (comp (ref "C40")
      (value "100n")
      (footprint "eagle-import:C025-025X050")
      (libsource (lib "eagle-import") (part "C-EU025-025X050"))
    )
    (comp (ref "C41")
      (value "470p")
      (footprint "eagle-import:C025-025X050")
      (libsource (lib "eagle-import") (part "C-EU025-025X050"))
    )
    (comp (ref "C42")
      (value "470p")
      (footprint "eagle-import:C025-025X050")
      (libsource (lib "eagle-import") (part "C-EU025-025X050"))
    )
    (comp (ref "C43")
      (value "100n")
      (footprint "eagle-import:C025-025X050")
      (libsource (lib "eagle-import") (part "C-EU025-025X050"))
    )
    (comp (ref "EXC")
      (value "EXC")
      (footprint "eagle-import:MA03-1")
      (libsource (lib "eagle-import") (part "MA03-1"))
    )
    (comp (ref "IC5")
      (value "LM6484")
      (footprint "eagle-import:DIL14")
      (libsource (lib "eagle-import") (part "LM324N"))
    )
    (comp (ref "IC7")
      (value "LM6484")
      (footprint "eagle-import:DIL14")
      (libsource (lib "eagle-import") (part "LM324N"))
    )
    (comp (ref "IC8")
      (value "4053N")
      (footprint "eagle-import:DIL16")
      (libsource (lib "eagle-import") (part "4053N"))
    )
    (comp (ref "IC12")
      (value "SSM2164P")
      (footprint "eagle-import:DIL16")
      (libsource (lib "eagle-import") (part "SSM2164P"))
    )
    (comp (ref "IC13")
      (value "LM6484")
      (footprint "eagle-import:DIL14")
      (libsource (lib "eagle-import") (part "LM324N"))
    )
    (comp (ref "P8")
      (value "2k")
      (footprint "eagle-import:RTRIM64Z")
      (libsource (lib "eagle-import") (part "R-TRIMM64Z"))
    )
    (comp (ref "P9")
      (value "20k")
      (footprint "eagle-import:RTRIM64Z")
      (libsource (lib "eagle-import") (part "R-TRIMM64Z"))
    )
    (comp (ref "P10")
      (value "20k")
      (footprint "eagle-import:RTRIM64Z")
      (libsource (lib "eagle-import") (part "R-TRIMM64Z"))
    )
    (comp (ref "P11")
      (value "20k")
      (footprint "eagle-import:RTRIM64Z")
      (libsource (lib "eagle-import") (part "R-TRIMM64Z"))
    )
    (comp (ref "R6")
      (value "150k")
      (footprint "eagle-import:0204_7")
      (libsource (lib "eagle-import") (part "R-EU_0204/7"))
    )
    (comp (ref "R7")
      (value "150k")
      (footprint "eagle-import:0204_7")
      (libsource (lib "eagle-import") (part "R-EU_0204/7"))
    )
    (comp (ref "R8")
      (value "150k")
      (footprint "eagle-import:0204_7")
      (libsource (lib "eagle-import") (part "R-EU_0204/7"))
    )
    (comp (ref "R9")
      (value "150k")
      (footprint "eagle-import:0204_7")
      (libsource (lib "eagle-import") (part "R-EU_0204/7"))
    )
    (comp (ref "R10")
      (value "150k")
      (footprint "eagle-import:0204_7")
      (libsource (lib "eagle-import") (part "R-EU_0204/7"))
    )
    (comp (ref "R11")
      (value "150k")
      (footprint "eagle-import:0204_7")
      (libsource (lib "eagle-import") (part "R-EU_0204/7"))
    )
    (comp (ref "R13")
      (value "47k")
      (footprint "eagle-import:0204_7")
      (libsource (lib "eagle-import") (part "R-EU_0204/7"))
    )
    (comp (ref "R14")
      (value "47k")
      (footprint "eagle-import:0204_7")
      (libsource (lib "eagle-import") (part "R-EU_0204/7"))
    )
    (comp (ref "R15")
      (value "47k")
      (footprint "eagle-import:0204_7")
      (libsource (lib "eagle-import") (part "R-EU_0204/7"))
    )
    (comp (ref "R16")
      (value "560")
      (footprint "eagle-import:0204_7")
      (libsource (lib "eagle-import") (part "R-EU_0204/7"))
    )
    (comp (ref "R17")
      (value "560")
      (footprint "eagle-import:0204_7")
      (libsource (lib "eagle-import") (part "R-EU_0204/7"))
    )
    (comp (ref "R18")
      (value "560")
      (footprint "eagle-import:0204_7")
      (libsource (lib "eagle-import") (part "R-EU_0204/7"))
    )
    (comp (ref "R19")
      (value "2k7")
      (footprint "eagle-import:0204_7")
      (libsource (lib "eagle-import") (part "R-EU_0204/7"))
    )
    (comp (ref "R20")
      (value "2k7")
      (footprint "eagle-import:0204_7")
      (libsource (lib "eagle-import") (part "R-EU_0204/7"))
    )
    (comp (ref "R21")
      (value "2k7")
      (footprint "eagle-import:0204_7")
      (libsource (lib "eagle-import") (part "R-EU_0204/7"))
    )
    (comp (ref "R29")
      (value "1k")
      (footprint "eagle-import:0204_7")
      (libsource (lib "eagle-import") (part "R-EU_0204/7"))
    )
    (comp (ref "R30")
      (value "1k")
      (footprint "eagle-import:0204_7")
      (libsource (lib "eagle-import") (part "R-EU_0204/7"))
    )
    (comp (ref "R31")
      (value "1k2")
      (footprint "eagle-import:0204_7")
      (libsource (lib "eagle-import") (part "R-EU_0204/7"))
    )
    (comp (ref "R32")
      (value "1k")
      (footprint "eagle-import:0204_7")
      (libsource (lib "eagle-import") (part "R-EU_0204/7"))
    )
    (comp (ref "R33")
      (value "560")
      (footprint "eagle-import:0204_7")
      (libsource (lib "eagle-import") (part "R-EU_0204/7"))
    )
    (comp (ref "R36")
      (value "47k")
      (footprint "eagle-import:0204_7")
      (libsource (lib "eagle-import") (part "R-EU_0204/7"))
    )
    (comp (ref "R37")
      (value "47k")
      (footprint "eagle-import:0204_7")
      (libsource (lib "eagle-import") (part "R-EU_0204/7"))
    )
    (comp (ref "R38")
      (value "47k")
      (footprint "eagle-import:0204_7")
      (libsource (lib "eagle-import") (part "R-EU_0204/7"))
    )
    (comp (ref "TP7")
      (value "TPSPAD1-13")
      (footprint "eagle-import:P1-13")
      (libsource (lib "eagle-import") (part "TPSPAD1-13"))
    )
    (comp (ref "TP8")
      (value "TPSPAD1-13")
      (footprint "eagle-import:P1-13")
      (libsource (lib "eagle-import") (part "TPSPAD1-13"))
    )
    (comp (ref "C52")
      (value "100n")
      (footprint "eagle-import:C025-025X050")
      (libsource (lib "eagle-import") (part "C-EU025-025X050"))
    )
    (comp (ref "C53")
      (value "100n")
      (footprint "eagle-import:C025-025X050")
      (libsource (lib "eagle-import") (part "C-EU025-025X050"))
    )
    (comp (ref "C54")
      (value "100n")
      (footprint "eagle-import:C025-025X050")
      (libsource (lib "eagle-import") (part "C-EU025-025X050"))
    )
    (comp (ref "C55")
      (value "100n")
      (footprint "eagle-import:C025-025X050")
      (libsource (lib "eagle-import") (part "C-EU025-025X050"))
    )
    (comp (ref "C56")
      (value "100n")
      (footprint "eagle-import:C025-025X050")
      (libsource (lib "eagle-import") (part "C-EU025-025X050"))
    )
    (comp (ref "D11")
      (value "1N4148")
      (footprint "eagle-import:DO35-7")
      (libsource (lib "eagle-import") (part "1N4148DO35-7"))
    )
    (comp (ref "D12")
      (value "1N4148")
      (footprint "eagle-import:DO35-7")
      (libsource (lib "eagle-import") (part "1N4148DO35-7"))
    )
    (comp (ref "D13")
      (value "1N4148")
      (footprint "eagle-import:DO35-7")
      (libsource (lib "eagle-import") (part "1N4148DO35-7"))
    )
    (comp (ref "D14")
      (value "1N4148")
      (footprint "eagle-import:DO35-7")
      (libsource (lib "eagle-import") (part "1N4148DO35-7"))
    )
    (comp (ref "D17")
      (value "1N4148")
      (footprint "eagle-import:DO35-7")
      (libsource (lib "eagle-import") (part "1N4148DO35-7"))
    )
    (comp (ref "IC21")
      (value "LM6484")
      (footprint "eagle-import:DIL14")
      (libsource (lib "eagle-import") (part "LM324N"))
    )
    (comp (ref "P5")
      (value "5k")
      (footprint "eagle-import:RTRIM64Z")
      (libsource (lib "eagle-import") (part "R-TRIMM64Z"))
    )
    (comp (ref "P6")
      (value "50k")
      (footprint "eagle-import:RTRIM64Z")
      (libsource (lib "eagle-import") (part "R-TRIMM64Z"))
    )
    (comp (ref "R47")
      (value "1k")
      (footprint "eagle-import:0204_7")
      (libsource (lib "eagle-import") (part "R-EU_0204/7"))
    )
    (comp (ref "R48")
      (value "33k")
      (footprint "eagle-import:0204_7")
      (libsource (lib "eagle-import") (part "R-EU_0204/7"))
    )
    (comp (ref "R74")
      (value "1k")
      (footprint "eagle-import:0204_7")
      (libsource (lib "eagle-import") (part "R-EU_0204/7"))
    )
    (comp (ref "R77")
      (value "1k")
      (footprint "eagle-import:0204_7")
      (libsource (lib "eagle-import") (part "R-EU_0204/7"))
    )
    (comp (ref "R78")
      (value "10k")
      (footprint "eagle-import:0204_7")
      (libsource (lib "eagle-import") (part "R-EU_0204/7"))
    )
    (comp (ref "R79")
      (value "1k")
      (footprint "eagle-import:0204_7")
      (libsource (lib "eagle-import") (part "R-EU_0204/7"))
    )
    (comp (ref "R80")
      (value "10k")
      (footprint "eagle-import:0204_7")
      (libsource (lib "eagle-import") (part "R-EU_0204/7"))
    )
    (comp (ref "R81")
      (value "10k")
      (footprint "eagle-import:0204_7")
      (libsource (lib "eagle-import") (part "R-EU_0204/7"))
    )
    (comp (ref "R82")
      (value "2k2")
      (footprint "eagle-import:0204_7")
      (libsource (lib "eagle-import") (part "R-EU_0204/7"))
    )
    (comp (ref "R83")
      (value "2M2")
      (footprint "eagle-import:0204_7")
      (libsource (lib "eagle-import") (part "R-EU_0204/7"))
    )
    (comp (ref "R86")
      (value "10k")
      (footprint "eagle-import:0204_7")
      (libsource (lib "eagle-import") (part "R-EU_0204/7"))
    )
    (comp (ref "R87")
      (value "10k")
      (footprint "eagle-import:0204_7")
      (libsource (lib "eagle-import") (part "R-EU_0204/7"))
    )
    (comp (ref "R88")
      (value "10k")
      (footprint "eagle-import:0204_7")
      (libsource (lib "eagle-import") (part "R-EU_0204/7"))
    )
    (comp (ref "R89")
      (value "150k")
      (footprint "eagle-import:0204_7")
      (libsource (lib "eagle-import") (part "R-EU_0204/7"))
    )
    (comp (ref "R90")
      (value "150k")
      (footprint "eagle-import:0204_7")
      (libsource (lib "eagle-import") (part "R-EU_0204/7"))
    )
    (comp (ref "TP5")
      (value "TPSPAD1-13")
      (footprint "eagle-import:P1-13")
      (libsource (lib "eagle-import") (part "TPSPAD1-13"))
    )
    (comp (ref "TP6")
      (value "TPSPAD1-13")
      (footprint "eagle-import:P1-13")
      (libsource (lib "eagle-import") (part "TPSPAD1-13"))
    )
  )
  (nets
    (net (code "1") (name "+5V") (class "Default")
      (node (ref "C10") (pin "2") (pinfunction "2_2") (pintype "passive"))
      (node (ref "C11") (pin "2") (pinfunction "2_2") (pintype "passive"))
      (node (ref "C2") (pin "2") (pinfunction "2_2") (pintype "passive"))
      (node (ref "C22") (pin "2") (pinfunction "2_2") (pintype "passive"))
      (node (ref "C24") (pin "2") (pinfunction "2_2") (pintype "passive"))
      (node (ref "C25") (pin "2") (pinfunction "2_2") (pintype "passive"))
      (node (ref "C28") (pin "2") (pinfunction "2_2") (pintype "passive"))
      (node (ref "C31") (pin "2") (pinfunction "2_2") (pintype "passive"))
      (node (ref "C32") (pin "2") (pinfunction "2_2") (pintype "passive"))
      (node (ref "C33") (pin "2") (pinfunction "2_2") (pintype "passive"))
      (node (ref "C34") (pin "2") (pinfunction "2_2") (pintype "passive"))
      (node (ref "C35") (pin "2") (pinfunction "2_2") (pintype "passive"))
      (node (ref "C37") (pin "2") (pinfunction "2_2") (pintype "passive"))
      (node (ref "C4") (pin "2") (pinfunction "2_2") (pintype "passive"))
      (node (ref "C43") (pin "2") (pinfunction "2_2") (pintype "passive"))
      (node (ref "C45") (pin "2") (pinfunction "2_2") (pintype "passive"))
      (node (ref "C48") (pin "2") (pinfunction "2_2") (pintype "passive"))
      (node (ref "C52") (pin "2") (pinfunction "2_2") (pintype "passive"))
      (node (ref "C56") (pin "2") (pinfunction "2_2") (pintype "passive"))
      (node (ref "C8") (pin "2") (pinfunction "2_2") (pintype "passive"))
      (node (ref "C9") (pin "+") (pinfunction "+_+") (pintype "passive"))
      (node (ref "DIAG") (pin "A") (pinfunction "A_A") (pintype "passive"))
      (node (ref "IC1") (pin "11") (pinfunction "VDD_11") (pintype "power_in"))
      (node (ref "IC1") (pin "32") (pinfunction "VDD_32") (pintype "power_in"))
      (node (ref "IC10") (pin "14") (pinfunction "VDD_14") (pintype "power_in"))
      (node (ref "IC11") (pin "13") (pinfunction "CD_13") (pintype "input"))
      (node (ref "IC11") (pin "16") (pinfunction "VDD_16") (pintype "power_in"))
      (node (ref "IC11") (pin "3") (pinfunction "CD_3") (pintype "input"))
      (node (ref "IC12") (pin "16") (pinfunction "V+_16") (pintype "power_in"))
      (node (ref "IC13") (pin "4") (pinfunction "V+_4") (pintype "power_in"))
      (node (ref "IC14") (pin "4") (pinfunction "V+_4") (pintype "power_in"))
      (node (ref "IC15") (pin "8") (pinfunction "V+_8") (pintype "power_in"))
      (node (ref "IC16") (pin "14") (pinfunction "VDD_14") (pintype "power_in"))
      (node (ref "IC17") (pin "13") (pinfunction "CD_13") (pintype "input"))
      (node (ref "IC17") (pin "16") (pinfunction "VDD_16") (pintype "power_in"))
      (node (ref "IC17") (pin "3") (pinfunction "CD_3") (pintype "input"))
      (node (ref "IC18") (pin "8") (pinfunction "V+_8") (pintype "power_in"))
      (node (ref "IC19") (pin "4") (pinfunction "V+_4") (pintype "power_in"))
      (node (ref "IC2") (pin "1") (pinfunction "VDD_1") (pintype "power_in"))
      (node (ref "IC20") (pin "4") (pinfunction "V+_4") (pintype "power_in"))
      (node (ref "IC21") (pin "4") (pinfunction "V+_4") (pintype "power_in"))
      (node (ref "IC3") (pin "1") (pinfunction "VDD_1") (pintype "power_in"))
      (node (ref "IC4") (pin "1") (pinfunction "VDD_1") (pintype "power_in"))
      (node (ref "IC5") (pin "4") (pinfunction "V+_4") (pintype "power_in"))
      (node (ref "IC6") (pin "1") (pinfunction "1-2EN_1") (pintype "input"))
      (node (ref "IC6") (pin "16") (pinfunction "VCC1_16") (pintype "power_in"))
      (node (ref "IC6") (pin "9") (pinfunction "3-4EN_9") (pintype "input"))
      (node (ref "IC7") (pin "4") (pinfunction "V+_4") (pintype "power_in"))
      (node (ref "IC8") (pin "16") (pinfunction "VCC_16") (pintype "power_in"))
      (node (ref "IC9") (pin "14") (pinfunction "VDD_14") (pintype "power_in"))
      (node (ref "POWER") (pin "1") (pinfunction "1_1") (pintype "passive"))
      (node (ref "R2") (pin "2") (pinfunction "2_2") (pintype "passive"))
      (node (ref "R28") (pin "1") (pinfunction "1_1") (pintype "passive"))
      (node (ref "R3") (pin "2") (pinfunction "2_2") (pintype "passive"))
      (node (ref "R34") (pin "1") (pinfunction "1_1") (pintype "passive"))
      (node (ref "R35") (pin "1") (pinfunction "1_1") (pintype "passive"))
      (node (ref "R66") (pin "2") (pinfunction "2_2") (pintype "passive"))
      (node (ref "R67") (pin "2") (pinfunction "2_2") (pintype "passive"))
      (node (ref "R75") (pin "1") (pinfunction "1_1") (pintype "passive"))
      (node (ref "R76") (pin "1") (pinfunction "1_1") (pintype "passive"))
      (node (ref "R82") (pin "2") (pinfunction "2_2") (pintype "passive"))
      (node (ref "R84") (pin "2") (pinfunction "2_2") (pintype "passive"))
      (node (ref "V+") (pin "3") (pinfunction "3_3") (pintype "passive"))
    )
    (net (code "2") (name "+24V") (class "Default")
      (node (ref "POWER") (pin "2") (pinfunction "2_2") (pintype "passive"))
      (node (ref "V+") (pin "1") (pinfunction "1_1") (pintype "passive"))
    )
    (net (code "3") (name "-5V") (class "Default")
      (node (ref "C1") (pin "2") (pinfunction "2_2") (pintype "passive"))
      (node (ref "C15") (pin "2") (pinfunction "2_2") (pintype "passive"))
      (node (ref "C23") (pin "2") (pinfunction "2_2") (pintype "passive"))
      (node (ref "C30") (pin "1") (pinfunction "1_1") (pintype "passive"))
      (node (ref "C39") (pin "2") (pinfunction "2_2") (pintype "passive"))
      (node (ref "C40") (pin "2") (pinfunction "2_2") (pintype "passive"))
      (node (ref "C44") (pin "2") (pinfunction "2_2") (pintype "passive"))
      (node (ref "C49") (pin "2") (pinfunction "2_2") (pintype "passive"))
      (node (ref "C53") (pin "2") (pinfunction "2_2") (pintype "passive"))
      (node (ref "IC12") (pin "9") (pinfunction "V-_9") (pintype "power_in"))
      (node (ref "IC13") (pin "11") (pinfunction "V-_11") (pintype "power_in"))
      (node (ref "IC14") (pin "11") (pinfunction "V-_11") (pintype "power_in"))
      (node (ref "IC19") (pin "11") (pinfunction "V-_11") (pintype "power_in"))
      (node (ref "IC20") (pin "11") (pinfunction "V-_11") (pintype "power_in"))
      (node (ref "IC21") (pin "11") (pinfunction "V-_11") (pintype "power_in"))
      (node (ref "IC5") (pin "11") (pinfunction "V-_11") (pintype "power_in"))
      (node (ref "IC7") (pin "11") (pinfunction "V-_11") (pintype "power_in"))
      (node (ref "IC8") (pin "7") (pinfunction "VEE_7") (pintype "power_in"))
      (node (ref "POWER") (pin "4") (pinfunction "4_4") (pintype "passive"))
    )
    (net (code "4") (name "CCOS") (class "Default")
      (node (ref "R48") (pin "2") (pinfunction "2_2") (pintype "passive"))
      (node (ref "REF2") (pin "7") (pinfunction "7_7") (pintype "passive"))
    )
    (net (code "5") (name "CRSCOS") (class "Default")
      (node (ref "D17") (pin "C") (pinfunction "C_C") (pintype "passive"))
      (node (ref "IC1") (pin "4") (pinfunction "RA2/AN2/VREF-/CVREF_4") (pintype "bidirectional"))
      (node (ref "R74") (pin "1") (pinfunction "1_1") (pintype "passive"))
    )
    (net (code "6") (name "CRSPER") (class "Default")
      (node (ref "IC1") (pin "27") (pinfunction "RD4/SPP4_27") (pintype "bidirectional"))
      (node (ref "IC9") (pin "1") (pinfunction "Q_1") (pintype "output"))
    )
    (net (code "7") (name "CRSQDT") (class "Default")
      (node (ref "IC1") (pin "25") (pinfunction "RC6/TX/CK_25") (pintype "bidirectional"))
      (node (ref "IC10") (pin "1") (pinfunction "Q_1") (pintype "output"))
    )
    (net (code "8") (name "CRSS1C") (class "Default")
      (node (ref "IC3") (pin "6") (pinfunction "VOUTB_6") (pintype "output"))
      (node (ref "R6") (pin "2") (pinfunction "2_2") (pintype "passive"))
    )
    (net (code "9") (name "CRSS1P") (class "Default")
      (node (ref "IC1") (pin "36") (pinfunction "RB3/AN9/CCP2/VPO_36") (pintype "bidirectional"))
      (node (ref "IC8") (pin "11") (pinfunction "A_11") (pintype "input"))
    )
    (net (code "10") (name "CRSS2C") (class "Default")
      (node (ref "IC4") (pin "6") (pinfunction "VOUTB_6") (pintype "output"))
      (node (ref "R11") (pin "2") (pinfunction "2_2") (pintype "passive"))
    )
    (net (code "11") (name "CRSS2P") (class "Default")
      (node (ref "IC1") (pin "30") (pinfunction "RD7/SPP7/P1D_30") (pintype "bidirectional"))
      (node (ref "IC8") (pin "10") (pinfunction "B_10") (pintype "input"))
    )
    (net (code "12") (name "CRSS3C") (class "Default")
      (node (ref "IC4") (pin "8") (pinfunction "VOUTA_8") (pintype "output"))
      (node (ref "R9") (pin "2") (pinfunction "2_2") (pintype "passive"))
    )
    (net (code "13") (name "CRSS3P") (class "Default")
      (node (ref "IC1") (pin "29") (pinfunction "RD6/SPP6/P1C_29") (pintype "bidirectional"))
      (node (ref "IC8") (pin "9") (pinfunction "C_9") (pintype "input"))
    )
    (net (code "14") (name "CRSSIN") (class "Default")
      (node (ref "D16") (pin "C") (pinfunction "C_C") (pintype "passive"))
      (node (ref "IC1") (pin "3") (pinfunction "RA1/AN1_3") (pintype "bidirectional"))
      (node (ref "R73") (pin "1") (pinfunction "1_1") (pintype "passive"))
    )
    (net (code "15") (name "CS1") (class "Default")
      (node (ref "IC1") (pin "16") (pinfunction "RC1/T1OSI/ICCP2/~{UOE}_16") (pintype "bidirectional"))
      (node (ref "IC3") (pin "2") (pinfunction "~{CS}_2") (pintype "input"))
    )
    (net (code "16") (name "CS2") (class "Default")
      (node (ref "IC1") (pin "8") (pinfunction "RE0/AN5/CK1SPP_8") (pintype "bidirectional"))
      (node (ref "IC2") (pin "2") (pinfunction "~{CS}_2") (pintype "input"))
    )
    (net (code "17") (name "CS3") (class "Default")
      (node (ref "IC1") (pin "15") (pinfunction "RC0/TIOSO/T13CKI_15") (pintype "bidirectional"))
      (node (ref "IC4") (pin "2") (pinfunction "~{CS}_2") (pintype "input"))
    )
    (net (code "18") (name "CSIN") (class "Default")
      (node (ref "R46") (pin "2") (pinfunction "2_2") (pintype "passive"))
      (node (ref "REF2") (pin "5") (pinfunction "5_5") (pintype "passive"))
    )
    (net (code "19") (name "DACCDI") (class "Default")
      (node (ref "IC14") (pin "10") (pinfunction "+IN_10") (pintype "input"))
      (node (ref "IC2") (pin "8") (pinfunction "VOUTA_8") (pintype "output"))
    )
    (net (code "20") (name "DACCRS") (class "Default")
      (node (ref "IC14") (pin "5") (pinfunction "+IN_5") (pintype "input"))
      (node (ref "IC2") (pin "6") (pinfunction "VOUTB_6") (pintype "output"))
    )
    (net (code "21") (name "DACHDG") (class "Default")
      (node (ref "IC14") (pin "3") (pinfunction "+IN_3") (pintype "input"))
      (node (ref "IC3") (pin "8") (pinfunction "VOUTA_8") (pintype "output"))
    )
    (net (code "22") (name "DOA_CLK") (class "Default")
      (node (ref "DOA") (pin "4") (pinfunction "4_4") (pintype "passive"))
      (node (ref "IC1") (pin "35") (pinfunction "RB2/AN8/INT2/VMO_35") (pintype "bidirectional"))
    )
    (net (code "23") (name "DOA_DAT") (class "Default")
      (node (ref "DOA") (pin "2") (pinfunction "2_2") (pintype "passive"))
      (node (ref "IC1") (pin "5") (pinfunction "RA3/AN3/VREF+_5") (pintype "bidirectional"))
    )
    (net (code "24") (name "FROM_FLAG") (class "Default")
      (node (ref "IC1") (pin "37") (pinfunction "RB4/AN11/KBI0/CSSPP_37") (pintype "bidirectional"))
      (node (ref "IC6") (pin "10") (pinfunction "3A_10") (pintype "input"))
    )
    (net (code "25") (name "GND") (class "Default")
      (node (ref "ANOUT") (pin "2") (pinfunction "2_2") (pintype "passive"))
      (node (ref "C1") (pin "1") (pinfunction "1_1") (pintype "passive"))
      (node (ref "C10") (pin "1") (pinfunction "1_1") (pintype "passive"))
      (node (ref "C11") (pin "1") (pinfunction "1_1") (pintype "passive"))
      (node (ref "C12") (pin "2") (pinfunction "2_2") (pintype "passive"))
      (node (ref "C13") (pin "2") (pinfunction "2_2") (pintype "passive"))
      (node (ref "C14") (pin "2") (pinfunction "2_2") (pintype "passive"))
      (node (ref "C15") (pin "1") (pinfunction "1_1") (pintype "passive"))
      (node (ref "C16") (pin "2") (pinfunction "2_2") (pintype "passive"))
      (node (ref "C19") (pin "2") (pinfunction "2_2") (pintype "passive"))
      (node (ref "C2") (pin "1") (pinfunction "1_1") (pintype "passive"))
      (node (ref "C20") (pin "2") (pinfunction "2_2") (pintype "passive"))
      (node (ref "C22") (pin "1") (pinfunction "1_1") (pintype "passive"))
      (node (ref "C23") (pin "1") (pinfunction "1_1") (pintype "passive"))
      (node (ref "C24") (pin "1") (pinfunction "1_1") (pintype "passive"))
      (node (ref "C25") (pin "1") (pinfunction "1_1") (pintype "passive"))
      (node (ref "C26") (pin "2") (pinfunction "2_2") (pintype "passive"))
      (node (ref "C27") (pin "2") (pinfunction "2_2") (pintype "passive"))
      (node (ref "C28") (pin "1") (pinfunction "1_1") (pintype "passive"))
      (node (ref "C3") (pin "1") (pinfunction "1_1") (pintype "passive"))
      (node (ref "C30") (pin "2") (pinfunction "2_2") (pintype "passive"))
      (node (ref "C31") (pin "1") (pinfunction "1_1") (pintype "passive"))
      (node (ref "C32") (pin "1") (pinfunction "1_1") (pintype "passive"))
      (node (ref "C33") (pin "1") (pinfunction "1_1") (pintype "passive"))
      (node (ref "C34") (pin "1") (pinfunction "1_1") (pintype "passive"))
      (node (ref "C35") (pin "1") (pinfunction "1_1") (pintype "passive"))
      (node (ref "C36") (pin "2") (pinfunction "2_2") (pintype "passive"))
      (node (ref "C37") (pin "1") (pinfunction "1_1") (pintype "passive"))
      (node (ref "C38") (pin "2") (pinfunction "2_2") (pintype "passive"))
      (node (ref "C39") (pin "1") (pinfunction "1_1") (pintype "passive"))
      (node (ref "C4") (pin "1") (pinfunction "1_1") (pintype "passive"))
      (node (ref "C40") (pin "1") (pinfunction "1_1") (pintype "passive"))
      (node (ref "C43") (pin "1") (pinfunction "1_1") (pintype "passive"))
      (node (ref "C44") (pin "1") (pinfunction "1_1") (pintype "passive"))
      (node (ref "C45") (pin "1") (pinfunction "1_1") (pintype "passive"))
      (node (ref "C46") (pin "1") (pinfunction "1_1") (pintype "passive"))
      (node (ref "C48") (pin "1") (pinfunction "1_1") (pintype "passive"))
      (node (ref "C49") (pin "1") (pinfunction "1_1") (pintype "passive"))
      (node (ref "C5") (pin "1") (pinfunction "1_1") (pintype "passive"))
      (node (ref "C51") (pin "1") (pinfunction "1_1") (pintype "passive"))
      (node (ref "C52") (pin "1") (pinfunction "1_1") (pintype "passive"))
      (node (ref "C53") (pin "1") (pinfunction "1_1") (pintype "passive"))
      (node (ref "C54") (pin "1") (pinfunction "1_1") (pintype "passive"))
      (node (ref "C56") (pin "1") (pinfunction "1_1") (pintype "passive"))
      (node (ref "C6") (pin "1") (pinfunction "1_1") (pintype "passive"))
      (node (ref "C7") (pin "2") (pinfunction "2_2") (pintype "passive"))
      (node (ref "C8") (pin "1") (pinfunction "1_1") (pintype "passive"))
      (node (ref "C9") (pin "-") (pinfunction "-_-") (pintype "passive"))
      (node (ref "D10") (pin "C") (pinfunction "C_C") (pintype "passive"))
      (node (ref "D13") (pin "A") (pinfunction "A_A") (pintype "passive"))
      (node (ref "D14") (pin "C") (pinfunction "C_C") (pintype "passive"))
      (node (ref "D15") (pin "A") (pinfunction "A_A") (pintype "passive"))
      (node (ref "D16") (pin "A") (pinfunction "A_A") (pintype "passive"))
      (node (ref "D17") (pin "A") (pinfunction "A_A") (pintype "passive"))
      (node (ref "D3") (pin "C") (pinfunction "C_C") (pintype "passive"))
      (node (ref "D4") (pin "A") (pinfunction "A_A") (pintype "passive"))
      (node (ref "D5") (pin "A") (pinfunction "A_A") (pintype "passive"))
      (node (ref "D6") (pin "C") (pinfunction "C_C") (pintype "passive"))
      (node (ref "D9") (pin "A") (pinfunction "A_A") (pintype "passive"))
      (node (ref "DOA") (pin "1") (pinfunction "1_1") (pintype "passive"))
      (node (ref "DOA") (pin "5") (pinfunction "5_5") (pintype "passive"))
      (node (ref "HSI2") (pin "2") (pinfunction "2_2") (pintype "passive"))
      (node (ref "HSI2") (pin "4") (pinfunction "4_4") (pintype "passive"))
      (node (ref "HSI2") (pin "6") (pinfunction "6_6") (pintype "passive"))
      (node (ref "HSI2") (pin "7") (pinfunction "7_7") (pintype "passive"))
      (node (ref "HSI2") (pin "8") (pinfunction "8_8") (pintype "passive"))
      (node (ref "IC1") (pin "12") (pinfunction "VSS_12") (pintype "power_in"))
      (node (ref "IC1") (pin "31") (pinfunction "VSS_31") (pintype "power_in"))
      (node (ref "IC10") (pin "10") (pinfunction "R_10") (pintype "input"))
      (node (ref "IC10") (pin "11") (pinfunction "CLK_11") (pintype "input"))
      (node (ref "IC10") (pin "4") (pinfunction "R_4") (pintype "input"))
      (node (ref "IC10") (pin "6") (pinfunction "S_6") (pintype "input"))
      (node (ref "IC10") (pin "7") (pinfunction "VSS_7") (pintype "power_in"))
      (node (ref "IC10") (pin "8") (pinfunction "S_8") (pintype "input"))
      (node (ref "IC10") (pin "9") (pinfunction "D_9") (pintype "input"))
      (node (ref "IC11") (pin "1") (pinfunction "T1_1") (pintype "input"))
      (node (ref "IC11") (pin "15") (pinfunction "T1_15") (pintype "input"))
      (node (ref "IC11") (pin "8") (pinfunction "VSS_8") (pintype "power_in"))
      (node (ref "IC12") (pin "14") (pinfunction "CTRL_14") (pintype "input"))
      (node (ref "IC12") (pin "15") (pinfunction "IN_15") (pintype "input"))
      (node (ref "IC12") (pin "8") (pinfunction "GND_8") (pintype "power_in"))
      (node (ref "IC13") (pin "10") (pinfunction "+IN_10") (pintype "input"))
      (node (ref "IC13") (pin "12") (pinfunction "+IN_12") (pintype "input"))
      (node (ref "IC13") (pin "3") (pinfunction "+IN_3") (pintype "input"))
      (node (ref "IC13") (pin "5") (pinfunction "+IN_5") (pintype "input"))
      (node (ref "IC15") (pin "2") (pinfunction "-IN_2") (pintype "input"))
      (node (ref "IC15") (pin "4") (pinfunction "V-_4") (pintype "power_in"))
      (node (ref "IC15") (pin "6") (pinfunction "-IN_6") (pintype "input"))
      (node (ref "IC16") (pin "5") (pinfunction "I0_5") (pintype "input"))
      (node (ref "IC16") (pin "6") (pinfunction "I1_6") (pintype "input"))
      (node (ref "IC16") (pin "7") (pinfunction "VSS_7") (pintype "power_in"))
      (node (ref "IC17") (pin "1") (pinfunction "T1_1") (pintype "input"))
      (node (ref "IC17") (pin "12") (pinfunction "A_12") (pintype "input"))
      (node (ref "IC17") (pin "15") (pinfunction "T1_15") (pintype "input"))
      (node (ref "IC17") (pin "8") (pinfunction "VSS_8") (pintype "power_in"))
      (node (ref "IC18") (pin "2") (pinfunction "-IN_2") (pintype "input"))
      (node (ref "IC18") (pin "4") (pinfunction "V-_4") (pintype "power_in"))
      (node (ref "IC18") (pin "6") (pinfunction "-IN_6") (pintype "input"))
      (node (ref "IC19") (pin "12") (pinfunction "+IN_12") (pintype "input"))
      (node (ref "IC2") (pin "7") (pinfunction "VSS_7") (pintype "power_in"))
      (node (ref "IC20") (pin "12") (pinfunction "+IN_12") (pintype "input"))
      (node (ref "IC21") (pin "12") (pinfunction "+IN_12") (pintype "input"))
      (node (ref "IC3") (pin "7") (pinfunction "VSS_7") (pintype "power_in"))
      (node (ref "IC4") (pin "7") (pinfunction "VSS_7") (pintype "power_in"))
      (node (ref "IC5") (pin "10") (pinfunction "+IN_10") (pintype "input"))
      (node (ref "IC6") (pin "12") (pinfunction "GND4_12") (pintype "power_in"))
      (node (ref "IC6") (pin "13") (pinfunction "GND3_13") (pintype "power_in"))
      (node (ref "IC6") (pin "4") (pinfunction "GND1_4") (pintype "power_in"))
      (node (ref "IC6") (pin "5") (pinfunction "GND2_5") (pintype "power_in"))
      (node (ref "IC7") (pin "12") (pinfunction "+IN_12") (pintype "input"))
      (node (ref "IC7") (pin "3") (pinfunction "+IN_3") (pintype "input"))
      (node (ref "IC7") (pin "5") (pinfunction "+IN_5") (pintype "input"))
      (node (ref "IC8") (pin "6") (pinfunction "INH_6") (pintype "input"))
      (node (ref "IC8") (pin "8") (pinfunction "GND_8") (pintype "power_in"))
      (node (ref "IC9") (pin "10") (pinfunction "R_10") (pintype "input"))
      (node (ref "IC9") (pin "4") (pinfunction "R_4") (pintype "input"))
      (node (ref "IC9") (pin "6") (pinfunction "S_6") (pintype "input"))
      (node (ref "IC9") (pin "7") (pinfunction "VSS_7") (pintype "power_in"))
      (node (ref "IC9") (pin "8") (pinfunction "S_8") (pintype "input"))
      (node (ref "OUT2") (pin "3") (pinfunction "3_3") (pintype "passive"))
      (node (ref "P10") (pin "1") (pinfunction "E_1") (pintype "passive"))
      (node (ref "P11") (pin "1") (pinfunction "E_1") (pintype "passive"))
      (node (ref "P9") (pin "1") (pinfunction "E_1") (pintype "passive"))
      (node (ref "POWER") (pin "3") (pinfunction "3_3") (pintype "passive"))
      (node (ref "POWER") (pin "5") (pinfunction "5_5") (pintype "passive"))
      (node (ref "R12") (pin "2") (pinfunction "2_2") (pintype "passive"))
      (node (ref "R32") (pin "2") (pinfunction "2_2") (pintype "passive"))
      (node (ref "R4") (pin "1") (pinfunction "1_1") (pintype "passive"))
      (node (ref "R40") (pin "1") (pinfunction "1_1") (pintype "passive"))
      (node (ref "R41") (pin "1") (pinfunction "1_1") (pintype "passive"))
      (node (ref "R43") (pin "1") (pinfunction "1_1") (pintype "passive"))
      (node (ref "R45") (pin "1") (pinfunction "1_1") (pintype "passive"))
      (node (ref "R47") (pin "1") (pinfunction "1_1") (pintype "passive"))
      (node (ref "R57") (pin "2") (pinfunction "2_2") (pintype "passive"))
      (node (ref "R60") (pin "1") (pinfunction "1_1") (pintype "passive"))
      (node (ref "R72") (pin "2") (pinfunction "2_2") (pintype "passive"))
      (node (ref "R79") (pin "1") (pinfunction "1_1") (pintype "passive"))
      (node (ref "R88") (pin "2") (pinfunction "2_2") (pintype "passive"))
      (node (ref "REF2") (pin "2") (pinfunction "2_2") (pintype "passive"))
      (node (ref "REF2") (pin "4") (pinfunction "4_4") (pintype "passive"))
      (node (ref "REF2") (pin "6") (pinfunction "6_6") (pintype "passive"))
      (node (ref "REF2") (pin "8") (pinfunction "8_8") (pintype "passive"))
      (node (ref "U/D") (pin "1") (pinfunction "1_1") (pintype "passive"))
      (node (ref "USB") (pin "4") (pinfunction "4_4") (pintype "passive"))
      (node (ref "USB") (pin "S1") (pinfunction "S1_S1") (pintype "passive"))
      (node (ref "USB") (pin "S2") (pinfunction "S2_S2") (pintype "passive"))
    )
    (net (code "26") (name "HDG000") (class "Default")
      (node (ref "IC1") (pin "28") (pinfunction "RD5/SPP5/P1B_28") (pintype "bidirectional"))
      (node (ref "IC9") (pin "13") (pinfunction "Q_13") (pintype "output"))
    )
    (net (code "27") (name "HDGSIG") (class "Default")
      (node (ref "D15") (pin "C") (pinfunction "C_C") (pintype "passive"))
      (node (ref "IC1") (pin "2") (pinfunction "RA0/AN0_2") (pintype "bidirectional"))
      (node (ref "R58") (pin "1") (pinfunction "1_1") (pintype "passive"))
    )
    (net (code "28") (name "LDAC1") (class "Default")
      (node (ref "IC1") (pin "9") (pinfunction "RE1/AN6/CK2SPP_9") (pintype "bidirectional"))
      (node (ref "IC3") (pin "5") (pinfunction "~{LDAC}_5") (pintype "input"))
    )
    (net (code "29") (name "LDAC2") (class "Default")
      (node (ref "IC1") (pin "21") (pinfunction "RD2/SPP2_21") (pintype "bidirectional"))
      (node (ref "IC2") (pin "5") (pinfunction "~{LDAC}_5") (pintype "input"))
    )
    (net (code "30") (name "LDAC3") (class "Default")
      (node (ref "IC1") (pin "10") (pinfunction "RE2/AN7/OESPP_10") (pintype "bidirectional"))
      (node (ref "IC4") (pin "5") (pinfunction "~{LDAC}_5") (pintype "input"))
    )
    (net (code "31") (name "MCLR") (class "Default")
      (node (ref "C3") (pin "2") (pinfunction "2_2") (pintype "passive"))
      (node (ref "DOA") (pin "3") (pinfunction "3_3") (pintype "passive"))
      (node (ref "IC1") (pin "1") (pinfunction "~{MCLR}/VPP/RE3_1") (pintype "input"))
      (node (ref "R3") (pin "1") (pinfunction "1_1") (pintype "passive"))
    )
    (net (code "32") (name "NAVWARN") (class "Default")
      (node (ref "IC1") (pin "38") (pinfunction "RB5/KBI1/PGM_38") (pintype "bidirectional"))
      (node (ref "IC6") (pin "7") (pinfunction "2A_7") (pintype "input"))
    )
    (net (code "33") (name "Net-(C12-Pad1)") (class "Default")
      (node (ref "C12") (pin "1") (pinfunction "1_1") (pintype "passive"))
      (node (ref "R17") (pin "1") (pinfunction "1_1") (pintype "passive"))
    )
    (net (code "34") (name "Net-(C13-Pad1)") (class "Default")
      (node (ref "C13") (pin "1") (pinfunction "1_1") (pintype "passive"))
      (node (ref "R18") (pin "1") (pinfunction "1_1") (pintype "passive"))
    )
    (net (code "35") (name "Net-(C14-Pad1)") (class "Default")
      (node (ref "C14") (pin "1") (pinfunction "1_1") (pintype "passive"))
      (node (ref "R16") (pin "1") (pinfunction "1_1") (pintype "passive"))
    )
    (net (code "36") (name "Net-(C17-Pad1)") (class "Default")
      (node (ref "C17") (pin "1") (pinfunction "1_1") (pintype "passive"))
      (node (ref "R6") (pin "1") (pinfunction "1_1") (pintype "passive"))
      (node (ref "R7") (pin "2") (pinfunction "2_2") (pintype "passive"))
    )
    (net (code "37") (name "Net-(C18-Pad1)") (class "Default")
      (node (ref "C18") (pin "1") (pinfunction "1_1") (pintype "passive"))
      (node (ref "R8") (pin "2") (pinfunction "2_2") (pintype "passive"))
      (node (ref "R9") (pin "1") (pinfunction "1_1") (pintype "passive"))
    )
    (net (code "38") (name "Net-(C21-Pad1)") (class "Default")
      (node (ref "C21") (pin "1") (pinfunction "1_1") (pintype "passive"))
      (node (ref "R10") (pin "2") (pinfunction "2_2") (pintype "passive"))
      (node (ref "R11") (pin "1") (pinfunction "1_1") (pintype "passive"))
    )
    (net (code "39") (name "Net-(C47-Pad1)") (class "Default")
      (node (ref "C47") (pin "1") (pinfunction "1_1") (pintype "passive"))
      (node (ref "R53") (pin "2") (pinfunction "2_2") (pintype "passive"))
      (node (ref "R54") (pin "1") (pinfunction "1_1") (pintype "passive"))
    )
    (net (code "40") (name "Net-(C50-Pad1)") (class "Default")
      (node (ref "C50") (pin "1") (pinfunction "1_1") (pintype "passive"))
      (node (ref "R68") (pin "1") (pinfunction "1_1") (pintype "passive"))
      (node (ref "R69") (pin "2") (pinfunction "2_2") (pintype "passive"))
    )
    (net (code "41") (name "Net-(C55-Pad1)") (class "Default")
      (node (ref "C55") (pin "1") (pinfunction "1_1") (pintype "passive"))
      (node (ref "R89") (pin "2") (pinfunction "2_2") (pintype "passive"))
      (node (ref "R90") (pin "1") (pinfunction "1_1") (pintype "passive"))
    )
    (net (code "42") (name "Net-(D1-PadC)") (class "Default")
      (node (ref "D1") (pin "C") (pinfunction "C_C") (pintype "passive"))
      (node (ref "R52") (pin "1") (pinfunction "1_1") (pintype "passive"))
      (node (ref "R54") (pin "2") (pinfunction "2_2") (pintype "passive"))
    )
    (net (code "43") (name "Net-(D7-PadC)") (class "Default")
      (node (ref "D7") (pin "C") (pinfunction "C_C") (pintype "passive"))
      (node (ref "R64") (pin "1") (pinfunction "1_1") (pintype "passive"))
      (node (ref "R68") (pin "2") (pinfunction "2_2") (pintype "passive"))
    )
    (net (code "44") (name "Net-(D11-PadC)") (class "Default")
      (node (ref "D11") (pin "C") (pinfunction "C_C") (pintype "passive"))
      (node (ref "R81") (pin "1") (pinfunction "1_1") (pintype "passive"))
      (node (ref "R90") (pin "2") (pinfunction "2_2") (pintype "passive"))
    )
    (net (code "45") (name "Net-(DIAG-C)") (class "Default")
      (node (ref "DIAG") (pin "K") (pinfunction "C_K") (pintype "passive"))
      (node (ref "R5") (pin "1") (pinfunction "1_1") (pintype "passive"))
    )
    (net (code "46") (name "Net-(HSI2-Pad1)") (class "Default")
      (node (ref "HSI2") (pin "1") (pinfunction "1_1") (pintype "passive"))
      (node (ref "R24") (pin "2") (pinfunction "2_2") (pintype "passive"))
    )
    (net (code "47") (name "Net-(HSI2-Pad3)") (class "Default")
      (node (ref "HSI2") (pin "3") (pinfunction "3_3") (pintype "passive"))
      (node (ref "R22") (pin "2") (pinfunction "2_2") (pintype "passive"))
    )
    (net (code "48") (name "Net-(HSI2-Pad9)") (class "Default")
      (node (ref "HSI2") (pin "9") (pinfunction "9_9") (pintype "passive"))
      (node (ref "R25") (pin "2") (pinfunction "2_2") (pintype "passive"))
    )
    (net (code "49") (name "Net-(HSI2-Pad10)") (class "Default")
      (node (ref "HSI2") (pin "10") (pinfunction "10_10") (pintype "passive"))
      (node (ref "R23") (pin "2") (pinfunction "2_2") (pintype "passive"))
    )
    (net (code "50") (name "Net-(IC1-OSC1{slash}CLKI)") (class "Default")
      (node (ref "C5") (pin "2") (pinfunction "2_2") (pintype "passive"))
      (node (ref "IC1") (pin "13") (pinfunction "OSC1/CLKI_13") (pintype "input"))
      (node (ref "Q1") (pin "2") (pinfunction "2_2") (pintype "passive"))
    )
    (net (code "51") (name "Net-(IC1-RA4{slash}T0CKI{slash}CIOUT{slash}RCV)") (class "Default")
      (node (ref "IC1") (pin "6") (pinfunction "RA4/T0CKI/CIOUT/RCV_6") (pintype "bidirectional"))
      (node (ref "R5") (pin "2") (pinfunction "2_2") (pintype "passive"))
    )
    (net (code "52") (name "Net-(IC1-RA6{slash}OSC2{slash}CLKO)") (class "Default")
      (node (ref "C6") (pin "2") (pinfunction "2_2") (pintype "passive"))
      (node (ref "IC1") (pin "14") (pinfunction "RA6/OSC2/CLKO_14") (pintype "output"))
      (node (ref "Q1") (pin "1") (pinfunction "1_1") (pintype "passive"))
    )
    (net (code "53") (name "Net-(IC1-RB0{slash}AN12{slash}INT0{slash}LFT0{slash}SDI{slash}SDA)") (class "Default")
      (node (ref "IC1") (pin "33") (pinfunction "RB0/AN12/INT0/LFT0/SDI/SDA_33") (pintype "bidirectional"))
      (node (ref "R12") (pin "1") (pinfunction "1_1") (pintype "passive"))
    )
    (net (code "54") (name "Net-(IC1-RC2{slash}CCP1{slash}P1A)") (class "Default")
      (node (ref "IC1") (pin "17") (pinfunction "RC2/CCP1/P1A_17") (pintype "bidirectional"))
      (node (ref "R1") (pin "2") (pinfunction "2_2") (pintype "passive"))
      (node (ref "R4") (pin "2") (pinfunction "2_2") (pintype "passive"))
    )
    (net (code "55") (name "Net-(IC1-RD0{slash}SPP0)") (class "Default")
      (node (ref "IC1") (pin "19") (pinfunction "RD0/SPP0_19") (pintype "bidirectional"))
      (node (ref "OUT2") (pin "1") (pinfunction "1_1") (pintype "passive"))
    )
    (net (code "56") (name "Net-(IC1-RD1{slash}SPP1)") (class "Default")
      (node (ref "IC1") (pin "20") (pinfunction "RD1/SPP1_20") (pintype "bidirectional"))
      (node (ref "OUT2") (pin "2") (pinfunction "2_2") (pintype "passive"))
    )
    (net (code "57") (name "Net-(IC1-VUSB)") (class "Default")
      (node (ref "C7") (pin "1") (pinfunction "1_1") (pintype "passive"))
      (node (ref "IC1") (pin "18") (pinfunction "VUSB_18") (pintype "bidirectional"))
    )
    (net (code "58") (name "Net-(IC5A-+IN)") (class "Default")
      (node (ref "C20") (pin "1") (pinfunction "1_1") (pintype "passive"))
      (node (ref "IC5") (pin "3") (pinfunction "+IN_3") (pintype "input"))
      (node (ref "R8") (pin "1") (pinfunction "1_1") (pintype "passive"))
    )
    (net (code "59") (name "Net-(IC5A--IN)") (class "Default")
      (node (ref "C18") (pin "2") (pinfunction "2_2") (pintype "passive"))
      (node (ref "IC5") (pin "1") (pinfunction "OUT_1") (pintype "output"))
      (node (ref "IC5") (pin "2") (pinfunction "-IN_2") (pintype "input"))
      (node (ref "R20") (pin "2") (pinfunction "2_2") (pintype "passive"))
    )
    (net (code "60") (name "Net-(IC5B-+IN)") (class "Default")
      (node (ref "C19") (pin "1") (pinfunction "1_1") (pintype "passive"))
      (node (ref "IC5") (pin "5") (pinfunction "+IN_5") (pintype "input"))
      (node (ref "R10") (pin "1") (pinfunction "1_1") (pintype "passive"))
    )
    (net (code "61") (name "Net-(IC5B--IN)") (class "Default")
      (node (ref "C21") (pin "2") (pinfunction "2_2") (pintype "passive"))
      (node (ref "IC5") (pin "6") (pinfunction "-IN_6") (pintype "input"))
      (node (ref "IC5") (pin "7") (pinfunction "OUT_7") (pintype "output"))
      (node (ref "R19") (pin "2") (pinfunction "2_2") (pintype "passive"))
    )
    (net (code "62") (name "Net-(IC5C--IN)") (class "Default")
      (node (ref "IC5") (pin "8") (pinfunction "OUT_8") (pintype "output"))
      (node (ref "IC5") (pin "9") (pinfunction "-IN_9") (pintype "input"))
    )
    (net (code "63") (name "Net-(IC5D-+IN)") (class "Default")
      (node (ref "C16") (pin "1") (pinfunction "1_1") (pintype "passive"))
      (node (ref "IC5") (pin "12") (pinfunction "+IN_12") (pintype "input"))
      (node (ref "R7") (pin "1") (pinfunction "1_1") (pintype "passive"))
    )
    (net (code "64") (name "Net-(IC5D--IN)") (class "Default")
      (node (ref "C17") (pin "2") (pinfunction "2_2") (pintype "passive"))
      (node (ref "IC5") (pin "13") (pinfunction "-IN_13") (pintype "input"))
      (node (ref "IC5") (pin "14") (pinfunction "OUT_14") (pintype "output"))
      (node (ref "R21") (pin "2") (pinfunction "2_2") (pintype "passive"))
    )
    (net (code "65") (name "Net-(IC6-1Y)") (class "Default")
      (node (ref "IC6") (pin "3") (pinfunction "1Y_3") (pintype "output"))
      (node (ref "R24") (pin "1") (pinfunction "1_1") (pintype "passive"))
    )
    (net (code "66") (name "Net-(IC6-2Y)") (class "Default")
      (node (ref "IC6") (pin "6") (pinfunction "2Y_6") (pintype "output"))
      (node (ref "R22") (pin "1") (pinfunction "1_1") (pintype "passive"))
    )
    (net (code "67") (name "Net-(IC6-3Y)") (class "Default")
      (node (ref "IC6") (pin "11") (pinfunction "3Y_11") (pintype "output"))
      (node (ref "R25") (pin "1") (pinfunction "1_1") (pintype "passive"))
    )
    (net (code "68") (name "Net-(IC6-4Y)") (class "Default")
      (node (ref "IC6") (pin "14") (pinfunction "4Y_14") (pintype "output"))
      (node (ref "R23") (pin "1") (pinfunction "1_1") (pintype "passive"))
    )
    (net (code "69") (name "Net-(IC7A--IN)") (class "Default")
      (node (ref "IC7") (pin "1") (pinfunction "OUT_1") (pintype "output"))
      (node (ref "IC7") (pin "2") (pinfunction "-IN_2") (pintype "input"))
    )
    (net (code "70") (name "Net-(IC7B--IN)") (class "Default")
      (node (ref "IC7") (pin "6") (pinfunction "-IN_6") (pintype "input"))
      (node (ref "IC7") (pin "7") (pinfunction "OUT_7") (pintype "output"))
    )
    (net (code "71") (name "Net-(IC7C-+IN)") (class "Default")
      (node (ref "IC7") (pin "10") (pinfunction "+IN_10") (pintype "input"))
      (node (ref "R30") (pin "1") (pinfunction "1_1") (pintype "passive"))
    )
    (net (code "72") (name "Net-(IC7C--IN)") (class "Default")
      (node (ref "IC7") (pin "9") (pinfunction "-IN_9") (pintype "input"))
      (node (ref "R31") (pin "2") (pinfunction "2_2") (pintype "passive"))
      (node (ref "R32") (pin "1") (pinfunction "1_1") (pintype "passive"))
    )
    (net (code "73") (name "Net-(IC7C-OUT)") (class "Default")
      (node (ref "IC7") (pin "8") (pinfunction "OUT_8") (pintype "output"))
      (node (ref "IC8") (pin "12") (pinfunction "X0_12") (pintype "bidirectional"))
      (node (ref "IC8") (pin "2") (pinfunction "Y0_2") (pintype "bidirectional"))
      (node (ref "IC8") (pin "5") (pinfunction "Z0_5") (pintype "bidirectional"))
      (node (ref "R31") (pin "1") (pinfunction "1_1") (pintype "passive"))
      (node (ref "TP7") (pin "TP") (pinfunction "PP_TP") (pintype "input"))
    )
    (net (code "74") (name "Net-(IC7D--IN)") (class "Default")
      (node (ref "IC7") (pin "13") (pinfunction "-IN_13") (pintype "input"))
      (node (ref "R29") (pin "1") (pinfunction "1_1") (pintype "passive"))
      (node (ref "R33") (pin "2") (pinfunction "2_2") (pintype "passive"))
    )
    (net (code "75") (name "Net-(IC7D-OUT)") (class "Default")
      (node (ref "IC7") (pin "14") (pinfunction "OUT_14") (pintype "output"))
      (node (ref "IC8") (pin "1") (pinfunction "Y1_1") (pintype "bidirectional"))
      (node (ref "IC8") (pin "13") (pinfunction "X1_13") (pintype "bidirectional"))
      (node (ref "IC8") (pin "3") (pinfunction "Z1_3") (pintype "bidirectional"))
      (node (ref "P8") (pin "2") (pinfunction "S_2") (pintype "passive"))
      (node (ref "P8") (pin "3") (pinfunction "A_3") (pintype "passive"))
      (node (ref "TP8") (pin "TP") (pinfunction "PP_TP") (pintype "input"))
    )
    (net (code "76") (name "Net-(IC8A-X)") (class "Default")
      (node (ref "IC8") (pin "14") (pinfunction "X_14") (pintype "bidirectional"))
      (node (ref "R15") (pin "2") (pinfunction "2_2") (pintype "passive"))
    )
    (net (code "77") (name "Net-(IC8A-Y)") (class "Default")
      (node (ref "IC8") (pin "15") (pinfunction "Y_15") (pintype "bidirectional"))
      (node (ref "R14") (pin "2") (pinfunction "2_2") (pintype "passive"))
    )
    (net (code "78") (name "Net-(IC8A-Z)") (class "Default")
      (node (ref "IC8") (pin "4") (pinfunction "Z_4") (pintype "bidirectional"))
      (node (ref "R13") (pin "2") (pinfunction "2_2") (pintype "passive"))
    )
    (net (code "79") (name "Net-(IC10A-CLK)") (class "Default")
      (node (ref "IC10") (pin "3") (pinfunction "CLK_3") (pintype "input"))
      (node (ref "IC11") (pin "11") (pinfunction "B_11") (pintype "input"))
      (node (ref "IC11") (pin "9") (pinfunction "~{Q}_9") (pintype "output"))
    )
    (net (code "80") (name "Net-(IC10A-D)") (class "Default")
      (node (ref "IC10") (pin "5") (pinfunction "D_5") (pintype "input"))
      (node (ref "IC11") (pin "12") (pinfunction "A_12") (pintype "input"))
      (node (ref "IC16") (pin "10") (pinfunction "O_10") (pintype "output"))
    )
    (net (code "81") (name "Net-(IC11A-A)") (class "Default")
      (node (ref "IC11") (pin "4") (pinfunction "A_4") (pintype "input"))
      (node (ref "IC16") (pin "3") (pinfunction "O_3") (pintype "output"))
      (node (ref "IC9") (pin "5") (pinfunction "D_5") (pintype "input"))
    )
    (net (code "82") (name "Net-(IC11A-B)") (class "Default")
      (node (ref "IC11") (pin "5") (pinfunction "B_5") (pintype "input"))
      (node (ref "IC11") (pin "7") (pinfunction "~{Q}_7") (pintype "output"))
      (node (ref "IC9") (pin "3") (pinfunction "CLK_3") (pintype "input"))
    )
    (net (code "83") (name "Net-(IC11A-T2)") (class "Default")
      (node (ref "C27") (pin "1") (pinfunction "1_1") (pintype "passive"))
      (node (ref "IC11") (pin "2") (pinfunction "T2_2") (pintype "input"))
      (node (ref "R35") (pin "2") (pinfunction "2_2") (pintype "passive"))
    )
    (net (code "84") (name "Net-(IC11B-T2)") (class "Default")
      (node (ref "C26") (pin "1") (pinfunction "1_1") (pintype "passive"))
      (node (ref "IC11") (pin "14") (pinfunction "T2_14") (pintype "input"))
      (node (ref "R34") (pin "2") (pinfunction "2_2") (pintype "passive"))
    )
    (net (code "85") (name "Net-(IC12A-CTRL)") (class "Default")
      (node (ref "IC12") (pin "3") (pinfunction "CTRL_3") (pintype "input"))
      (node (ref "R21") (pin "1") (pinfunction "1_1") (pintype "passive"))
    )
    (net (code "86") (name "Net-(IC12A-IN)") (class "Default")
      (node (ref "IC12") (pin "2") (pinfunction "IN_2") (pintype "input"))
      (node (ref "R15") (pin "1") (pinfunction "1_1") (pintype "passive"))
      (node (ref "R16") (pin "2") (pinfunction "2_2") (pintype "passive"))
    )
    (net (code "87") (name "Net-(IC12A-OUT)") (class "Default")
      (node (ref "C29") (pin "1") (pinfunction "1_1") (pintype "passive"))
      (node (ref "IC12") (pin "4") (pinfunction "OUT_4") (pintype "output"))
      (node (ref "IC13") (pin "2") (pinfunction "-IN_2") (pintype "input"))
      (node (ref "R36") (pin "2") (pinfunction "2_2") (pintype "passive"))
    )
    (net (code "88") (name "Net-(IC12B-CTRL)") (class "Default")
      (node (ref "IC12") (pin "6") (pinfunction "CTRL_6") (pintype "input"))
      (node (ref "R19") (pin "1") (pinfunction "1_1") (pintype "passive"))
    )
    (net (code "89") (name "Net-(IC12B-IN)") (class "Default")
      (node (ref "IC12") (pin "7") (pinfunction "IN_7") (pintype "input"))
      (node (ref "R14") (pin "1") (pinfunction "1_1") (pintype "passive"))
      (node (ref "R18") (pin "2") (pinfunction "2_2") (pintype "passive"))
    )
    (net (code "90") (name "Net-(IC12B-OUT)") (class "Default")
      (node (ref "C42") (pin "1") (pinfunction "1_1") (pintype "passive"))
      (node (ref "IC12") (pin "5") (pinfunction "OUT_5") (pintype "output"))
      (node (ref "IC13") (pin "9") (pinfunction "-IN_9") (pintype "input"))
      (node (ref "R38") (pin "2") (pinfunction "2_2") (pintype "passive"))
    )
    (net (code "91") (name "Net-(IC12C-CTRL)") (class "Default")
      (node (ref "IC12") (pin "11") (pinfunction "CTRL_11") (pintype "input"))
      (node (ref "R20") (pin "1") (pinfunction "1_1") (pintype "passive"))
    )
    (net (code "92") (name "Net-(IC12C-IN)") (class "Default")
      (node (ref "IC12") (pin "10") (pinfunction "IN_10") (pintype "input"))
      (node (ref "R13") (pin "1") (pinfunction "1_1") (pintype "passive"))
      (node (ref "R17") (pin "2") (pinfunction "2_2") (pintype "passive"))
    )
    (net (code "93") (name "Net-(IC12C-OUT)") (class "Default")
      (node (ref "C41") (pin "1") (pinfunction "1_1") (pintype "passive"))
      (node (ref "IC12") (pin "12") (pinfunction "OUT_12") (pintype "output"))
      (node (ref "IC13") (pin "13") (pinfunction "-IN_13") (pintype "input"))
      (node (ref "R37") (pin "2") (pinfunction "2_2") (pintype "passive"))
    )
    (net (code "94") (name "Net-(IC13A-OUT)") (class "Default")
      (node (ref "C29") (pin "2") (pinfunction "2_2") (pintype "passive"))
      (node (ref "IC13") (pin "1") (pinfunction "OUT_1") (pintype "output"))
      (node (ref "P9") (pin "3") (pinfunction "A_3") (pintype "passive"))
      (node (ref "R36") (pin "1") (pinfunction "1_1") (pintype "passive"))
    )
    (net (code "95") (name "Net-(IC13B--IN)") (class "Default")
      (node (ref "IC13") (pin "6") (pinfunction "-IN_6") (pintype "input"))
      (node (ref "IC13") (pin "7") (pinfunction "OUT_7") (pintype "output"))
    )
    (net (code "96") (name "Net-(IC13C-OUT)") (class "Default")
      (node (ref "C42") (pin "2") (pinfunction "2_2") (pintype "passive"))
      (node (ref "IC13") (pin "8") (pinfunction "OUT_8") (pintype "output"))
      (node (ref "P10") (pin "3") (pinfunction "A_3") (pintype "passive"))
      (node (ref "R38") (pin "1") (pinfunction "1_1") (pintype "passive"))
    )
    (net (code "97") (name "Net-(IC13D-OUT)") (class "Default")
      (node (ref "C41") (pin "2") (pinfunction "2_2") (pintype "passive"))
      (node (ref "IC13") (pin "14") (pinfunction "OUT_14") (pintype "output"))
      (node (ref "P11") (pin "3") (pinfunction "A_3") (pintype "passive"))
      (node (ref "R37") (pin "1") (pinfunction "1_1") (pintype "passive"))
    )
    (net (code "98") (name "Net-(IC14A--IN)") (class "Default")
      (node (ref "ANOUT") (pin "3") (pinfunction "3_3") (pintype "passive"))
      (node (ref "IC14") (pin "1") (pinfunction "OUT_1") (pintype "output"))
      (node (ref "IC14") (pin "2") (pinfunction "-IN_2") (pintype "input"))
    )
    (net (code "99") (name "Net-(IC14B--IN)") (class "Default")
      (node (ref "ANOUT") (pin "1") (pinfunction "1_1") (pintype "passive"))
      (node (ref "IC14") (pin "6") (pinfunction "-IN_6") (pintype "input"))
      (node (ref "IC14") (pin "7") (pinfunction "OUT_7") (pintype "output"))
    )
    (net (code "100") (name "Net-(IC14C--IN)") (class "Default")
      (node (ref "IC14") (pin "9") (pinfunction "-IN_9") (pintype "input"))
      (node (ref "R27") (pin "1") (pinfunction "1_1") (pintype "passive"))
      (node (ref "R28") (pin "2") (pinfunction "2_2") (pintype "passive"))
    )
    (net (code "101") (name "Net-(IC14C-OUT)") (class "Default")
      (node (ref "IC14") (pin "8") (pinfunction "OUT_8") (pintype "output"))
      (node (ref "R26") (pin "1") (pinfunction "1_1") (pintype "passive"))
      (node (ref "R27") (pin "2") (pinfunction "2_2") (pintype "passive"))
    )
    (net (code "102") (name "Net-(IC14D-+IN)") (class "Default")
      (node (ref "IC14") (pin "12") (pinfunction "+IN_12") (pintype "input"))
      (node (ref "R39") (pin "1") (pinfunction "1_1") (pintype "passive"))
      (node (ref "R40") (pin "2") (pinfunction "2_2") (pintype "passive"))
    )
    (net (code "103") (name "Net-(IC15A-+IN)") (class "Default")
      (node (ref "D3") (pin "A") (pinfunction "A_A") (pintype "passive"))
      (node (ref "D4") (pin "C") (pinfunction "C_C") (pintype "passive"))
      (node (ref "IC15") (pin "3") (pinfunction "+IN_3") (pintype "input"))
      (node (ref "R50") (pin "1") (pinfunction "1_1") (pintype "passive"))
      (node (ref "R59") (pin "2") (pinfunction "2_2") (pintype "passive"))
    )
    (net (code "104") (name "Net-(IC15B-+IN)") (class "Default")
      (node (ref "D5") (pin "C") (pinfunction "C_C") (pintype "passive"))
      (node (ref "D6") (pin "A") (pinfunction "A_A") (pintype "passive"))
      (node (ref "IC15") (pin "5") (pinfunction "+IN_5") (pintype "input"))
      (node (ref "R51") (pin "1") (pinfunction "1_1") (pintype "passive"))
      (node (ref "R65") (pin "2") (pinfunction "2_2") (pintype "passive"))
    )
    (net (code "105") (name "Net-(IC16D-O)") (class "Default")
      (node (ref "IC16") (pin "11") (pinfunction "O_11") (pintype "output"))
      (node (ref "IC17") (pin "4") (pinfunction "A_4") (pintype "input"))
      (node (ref "IC9") (pin "9") (pinfunction "D_9") (pintype "input"))
    )
    (net (code "106") (name "Net-(IC17A-B)") (class "Default")
      (node (ref "IC17") (pin "5") (pinfunction "B_5") (pintype "input"))
      (node (ref "IC17") (pin "7") (pinfunction "~{Q}_7") (pintype "output"))
      (node (ref "IC9") (pin "11") (pinfunction "CLK_11") (pintype "input"))
    )
    (net (code "107") (name "Net-(IC17A-T2)") (class "Default")
      (node (ref "C36") (pin "1") (pinfunction "1_1") (pintype "passive"))
      (node (ref "IC17") (pin "2") (pinfunction "T2_2") (pintype "input"))
      (node (ref "R76") (pin "2") (pinfunction "2_2") (pintype "passive"))
    )
    (net (code "108") (name "Net-(IC17B-T2)") (class "Default")
      (node (ref "C38") (pin "1") (pinfunction "1_1") (pintype "passive"))
      (node (ref "IC17") (pin "14") (pinfunction "T2_14") (pintype "input"))
      (node (ref "R75") (pin "2") (pinfunction "2_2") (pintype "passive"))
    )
    (net (code "109") (name "Net-(IC18A-+IN)") (class "Default")
      (node (ref "D13") (pin "C") (pinfunction "C_C") (pintype "passive"))
      (node (ref "D14") (pin "A") (pinfunction "A_A") (pintype "passive"))
      (node (ref "IC18") (pin "3") (pinfunction "+IN_3") (pintype "input"))
      (node (ref "R78") (pin "1") (pinfunction "1_1") (pintype "passive"))
      (node (ref "R83") (pin "2") (pinfunction "2_2") (pintype "passive"))
    )
    (net (code "110") (name "Net-(IC18B-+IN)") (class "Default")
      (node (ref "D10") (pin "A") (pinfunction "A_A") (pintype "passive"))
      (node (ref "D9") (pin "C") (pinfunction "C_C") (pintype "passive"))
      (node (ref "IC18") (pin "5") (pinfunction "+IN_5") (pintype "input"))
      (node (ref "R63") (pin "1") (pinfunction "1_1") (pintype "passive"))
      (node (ref "R85") (pin "2") (pinfunction "2_2") (pintype "passive"))
    )
    (net (code "111") (name "Net-(IC19A-+IN)") (class "Default")
      (node (ref "IC19") (pin "3") (pinfunction "+IN_3") (pintype "input"))
      (node (ref "R44") (pin "1") (pinfunction "1_1") (pintype "passive"))
    )
    (net (code "112") (name "Net-(IC19A--IN)") (class "Default")
      (node (ref "IC19") (pin "2") (pinfunction "-IN_2") (pintype "input"))
      (node (ref "P1") (pin "1") (pinfunction "E_1") (pintype "passive"))
      (node (ref "R43") (pin "2") (pinfunction "2_2") (pintype "passive"))
    )
    (net (code "113") (name "Net-(IC19A-OUT)") (class "Default")
      (node (ref "IC19") (pin "1") (pinfunction "OUT_1") (pintype "output"))
      (node (ref "P1") (pin "2") (pinfunction "S_2") (pintype "passive"))
      (node (ref "P1") (pin "3") (pinfunction "A_3") (pintype "passive"))
      (node (ref "R49") (pin "2") (pinfunction "2_2") (pintype "passive"))
      (node (ref "R51") (pin "2") (pinfunction "2_2") (pintype "passive"))
      (node (ref "TP1") (pin "TP") (pinfunction "PP_TP") (pintype "input"))
    )
    (net (code "114") (name "Net-(IC19B-+IN)") (class "Default")
      (node (ref "IC19") (pin "5") (pinfunction "+IN_5") (pintype "input"))
      (node (ref "R55") (pin "1") (pinfunction "1_1") (pintype "passive"))
    )
    (net (code "115") (name "Net-(IC19B--IN)") (class "Default")
      (node (ref "IC19") (pin "6") (pinfunction "-IN_6") (pintype "input"))
      (node (ref "R56") (pin "2") (pinfunction "2_2") (pintype "passive"))
      (node (ref "R57") (pin "1") (pinfunction "1_1") (pintype "passive"))
    )
    (net (code "116") (name "Net-(IC19B-OUT)") (class "Default")
      (node (ref "IC19") (pin "7") (pinfunction "OUT_7") (pintype "output"))
      (node (ref "P2") (pin "2") (pinfunction "S_2") (pintype "passive"))
      (node (ref "P2") (pin "3") (pinfunction "A_3") (pintype "passive"))
      (node (ref "R58") (pin "2") (pinfunction "2_2") (pintype "passive"))
      (node (ref "TP2") (pin "TP") (pinfunction "PP_TP") (pintype "input"))
    )
    (net (code "117") (name "Net-(IC19C-+IN)") (class "Default")
      (node (ref "C46") (pin "2") (pinfunction "2_2") (pintype "passive"))
      (node (ref "IC19") (pin "10") (pinfunction "+IN_10") (pintype "input"))
      (node (ref "R53") (pin "1") (pinfunction "1_1") (pintype "passive"))
    )
    (net (code "118") (name "Net-(IC19C--IN)") (class "Default")
      (node (ref "C47") (pin "2") (pinfunction "2_2") (pintype "passive"))
      (node (ref "IC19") (pin "8") (pinfunction "OUT_8") (pintype "output"))
      (node (ref "IC19") (pin "9") (pinfunction "-IN_9") (pintype "input"))
      (node (ref "R55") (pin "2") (pinfunction "2_2") (pintype "passive"))
    )
    (net (code "119") (name "Net-(IC19D--IN)") (class "Default")
      (node (ref "D2") (pin "A") (pinfunction "A_A") (pintype "passive"))
      (node (ref "IC19") (pin "13") (pinfunction "-IN_13") (pintype "input"))
      (node (ref "R49") (pin "1") (pinfunction "1_1") (pintype "passive"))
      (node (ref "R52") (pin "2") (pinfunction "2_2") (pintype "passive"))
    )
    (net (code "120") (name "Net-(IC19D-OUT)") (class "Default")
      (node (ref "D1") (pin "A") (pinfunction "A_A") (pintype "passive"))
      (node (ref "D2") (pin "C") (pinfunction "C_C") (pintype "passive"))
      (node (ref "IC19") (pin "14") (pinfunction "OUT_14") (pintype "output"))
    )
    (net (code "121") (name "Net-(IC20A-+IN)") (class "Default")
      (node (ref "IC20") (pin "3") (pinfunction "+IN_3") (pintype "input"))
      (node (ref "R62") (pin "1") (pinfunction "1_1") (pintype "passive"))
    )
    (net (code "122") (name "Net-(IC20A--IN)") (class "Default")
      (node (ref "IC20") (pin "2") (pinfunction "-IN_2") (pintype "input"))
      (node (ref "P3") (pin "1") (pinfunction "E_1") (pintype "passive"))
      (node (ref "R60") (pin "2") (pinfunction "2_2") (pintype "passive"))
    )
    (net (code "123") (name "Net-(IC20A-OUT)") (class "Default")
      (node (ref "IC20") (pin "1") (pinfunction "OUT_1") (pintype "output"))
      (node (ref "P3") (pin "2") (pinfunction "S_2") (pintype "passive"))
      (node (ref "P3") (pin "3") (pinfunction "A_3") (pintype "passive"))
      (node (ref "R61") (pin "2") (pinfunction "2_2") (pintype "passive"))
      (node (ref "R63") (pin "2") (pinfunction "2_2") (pintype "passive"))
      (node (ref "TP3") (pin "TP") (pinfunction "PP_TP") (pintype "input"))
    )
    (net (code "124") (name "Net-(IC20B-+IN)") (class "Default")
      (node (ref "IC20") (pin "5") (pinfunction "+IN_5") (pintype "input"))
      (node (ref "R70") (pin "1") (pinfunction "1_1") (pintype "passive"))
    )
    (net (code "125") (name "Net-(IC20B--IN)") (class "Default")
      (node (ref "IC20") (pin "6") (pinfunction "-IN_6") (pintype "input"))
      (node (ref "R71") (pin "2") (pinfunction "2_2") (pintype "passive"))
      (node (ref "R72") (pin "1") (pinfunction "1_1") (pintype "passive"))
    )
    (net (code "126") (name "Net-(IC20B-OUT)") (class "Default")
      (node (ref "IC20") (pin "7") (pinfunction "OUT_7") (pintype "output"))
      (node (ref "P4") (pin "2") (pinfunction "S_2") (pintype "passive"))
      (node (ref "P4") (pin "3") (pinfunction "A_3") (pintype "passive"))
      (node (ref "R73") (pin "2") (pinfunction "2_2") (pintype "passive"))
      (node (ref "TP4") (pin "TP") (pinfunction "PP_TP") (pintype "input"))
    )
    (net (code "127") (name "Net-(IC20C-+IN)") (class "Default")
      (node (ref "C51") (pin "2") (pinfunction "2_2") (pintype "passive"))
      (node (ref "IC20") (pin "10") (pinfunction "+IN_10") (pintype "input"))
      (node (ref "R69") (pin "1") (pinfunction "1_1") (pintype "passive"))
    )
    (net (code "128") (name "Net-(IC20C--IN)") (class "Default")
      (node (ref "C50") (pin "2") (pinfunction "2_2") (pintype "passive"))
      (node (ref "IC20") (pin "8") (pinfunction "OUT_8") (pintype "output"))
      (node (ref "IC20") (pin "9") (pinfunction "-IN_9") (pintype "input"))
      (node (ref "R70") (pin "2") (pinfunction "2_2") (pintype "passive"))
    )
    (net (code "129") (name "Net-(IC20D--IN)") (class "Default")
      (node (ref "D8") (pin "A") (pinfunction "A_A") (pintype "passive"))
      (node (ref "IC20") (pin "13") (pinfunction "-IN_13") (pintype "input"))
      (node (ref "R61") (pin "1") (pinfunction "1_1") (pintype "passive"))
      (node (ref "R64") (pin "2") (pinfunction "2_2") (pintype "passive"))
    )
    (net (code "130") (name "Net-(IC20D-OUT)") (class "Default")
      (node (ref "D7") (pin "A") (pinfunction "A_A") (pintype "passive"))
      (node (ref "D8") (pin "C") (pinfunction "C_C") (pintype "passive"))
      (node (ref "IC20") (pin "14") (pinfunction "OUT_14") (pintype "output"))
    )
    (net (code "131") (name "Net-(IC21A-+IN)") (class "Default")
      (node (ref "IC21") (pin "3") (pinfunction "+IN_3") (pintype "input"))
      (node (ref "R77") (pin "1") (pinfunction "1_1") (pintype "passive"))
    )
    (net (code "132") (name "Net-(IC21A--IN)") (class "Default")
      (node (ref "IC21") (pin "2") (pinfunction "-IN_2") (pintype "input"))
      (node (ref "P5") (pin "1") (pinfunction "E_1") (pintype "passive"))
      (node (ref "R79") (pin "2") (pinfunction "2_2") (pintype "passive"))
    )
    (net (code "133") (name "Net-(IC21A-OUT)") (class "Default")
      (node (ref "IC21") (pin "1") (pinfunction "OUT_1") (pintype "output"))
      (node (ref "P5") (pin "2") (pinfunction "S_2") (pintype "passive"))
      (node (ref "P5") (pin "3") (pinfunction "A_3") (pintype "passive"))
      (node (ref "R78") (pin "2") (pinfunction "2_2") (pintype "passive"))
      (node (ref "R80") (pin "2") (pinfunction "2_2") (pintype "passive"))
      (node (ref "TP5") (pin "TP") (pinfunction "PP_TP") (pintype "input"))
    )
    (net (code "134") (name "Net-(IC21B-+IN)") (class "Default")
      (node (ref "IC21") (pin "5") (pinfunction "+IN_5") (pintype "input"))
      (node (ref "R86") (pin "1") (pinfunction "1_1") (pintype "passive"))
    )
    (net (code "135") (name "Net-(IC21B--IN)") (class "Default")
      (node (ref "IC21") (pin "6") (pinfunction "-IN_6") (pintype "input"))
      (node (ref "R87") (pin "2") (pinfunction "2_2") (pintype "passive"))
      (node (ref "R88") (pin "1") (pinfunction "1_1") (pintype "passive"))
    )
    (net (code "136") (name "Net-(IC21B-OUT)") (class "Default")
      (node (ref "IC21") (pin "7") (pinfunction "OUT_7") (pintype "output"))
      (node (ref "P6") (pin "2") (pinfunction "S_2") (pintype "passive"))
      (node (ref "P6") (pin "3") (pinfunction "A_3") (pintype "passive"))
      (node (ref "R74") (pin "2") (pinfunction "2_2") (pintype "passive"))
      (node (ref "TP6") (pin "TP") (pinfunction "PP_TP") (pintype "input"))
    )
    (net (code "137") (name "Net-(IC21C-+IN)") (class "Default")
      (node (ref "C54") (pin "2") (pinfunction "2_2") (pintype "passive"))
      (node (ref "IC21") (pin "10") (pinfunction "+IN_10") (pintype "input"))
      (node (ref "R89") (pin "1") (pinfunction "1_1") (pintype "passive"))
    )
    (net (code "138") (name "Net-(IC21C--IN)") (class "Default")
      (node (ref "C55") (pin "2") (pinfunction "2_2") (pintype "passive"))
      (node (ref "IC21") (pin "8") (pinfunction "OUT_8") (pintype "output"))
      (node (ref "IC21") (pin "9") (pinfunction "-IN_9") (pintype "input"))
      (node (ref "R86") (pin "2") (pinfunction "2_2") (pintype "passive"))
    )
    (net (code "139") (name "Net-(IC21D--IN)") (class "Default")
      (node (ref "D12") (pin "A") (pinfunction "A_A") (pintype "passive"))
      (node (ref "IC21") (pin "13") (pinfunction "-IN_13") (pintype "input"))
      (node (ref "R80") (pin "1") (pinfunction "1_1") (pintype "passive"))
      (node (ref "R81") (pin "2") (pinfunction "2_2") (pintype "passive"))
    )
    (net (code "140") (name "Net-(IC21D-OUT)") (class "Default")
      (node (ref "D11") (pin "A") (pinfunction "A_A") (pintype "passive"))
      (node (ref "D12") (pin "C") (pinfunction "C_C") (pintype "passive"))
      (node (ref "IC21") (pin "14") (pinfunction "OUT_14") (pintype "output"))
    )
    (net (code "141") (name "Net-(P2-E)") (class "Default")
      (node (ref "P2") (pin "1") (pinfunction "E_1") (pintype "passive"))
      (node (ref "R56") (pin "1") (pinfunction "1_1") (pintype "passive"))
    )
    (net (code "142") (name "Net-(P4-E)") (class "Default")
      (node (ref "P4") (pin "1") (pinfunction "E_1") (pintype "passive"))
      (node (ref "R71") (pin "1") (pinfunction "1_1") (pintype "passive"))
    )
    (net (code "143") (name "Net-(P6-E)") (class "Default")
      (node (ref "P6") (pin "1") (pinfunction "E_1") (pintype "passive"))
      (node (ref "R87") (pin "1") (pinfunction "1_1") (pintype "passive"))
    )
    (net (code "144") (name "Net-(P7-A)") (class "Default")
      (node (ref "HSI2") (pin "5") (pinfunction "5_5") (pintype "passive"))
      (node (ref "P7") (pin "2") (pinfunction "S_2") (pintype "passive"))
      (node (ref "P7") (pin "3") (pinfunction "A_3") (pintype "passive"))
    )
    (net (code "145") (name "Net-(P7-E)") (class "Default")
      (node (ref "P7") (pin "1") (pinfunction "E_1") (pintype "passive"))
      (node (ref "R26") (pin "2") (pinfunction "2_2") (pintype "passive"))
    )
    (net (code "146") (name "Net-(P8-E)") (class "Default")
      (node (ref "P8") (pin "1") (pinfunction "E_1") (pintype "passive"))
      (node (ref "R33") (pin "1") (pinfunction "1_1") (pintype "passive"))
    )
    (net (code "147") (name "Net-(P9-S)") (class "Default")
      (node (ref "EXC") (pin "1") (pinfunction "1_1") (pintype "passive"))
      (node (ref "P9") (pin "2") (pinfunction "S_2") (pintype "passive"))
    )
    (net (code "148") (name "Net-(P10-S)") (class "Default")
      (node (ref "EXC") (pin "2") (pinfunction "2_2") (pintype "passive"))
      (node (ref "P10") (pin "2") (pinfunction "S_2") (pintype "passive"))
    )
    (net (code "149") (name "Net-(P11-S)") (class "Default")
      (node (ref "EXC") (pin "3") (pinfunction "3_3") (pintype "passive"))
      (node (ref "P11") (pin "2") (pinfunction "S_2") (pintype "passive"))
    )
    (net (code "150") (name "Net-(R1-Pad1)") (class "Default")
      (node (ref "R1") (pin "1") (pinfunction "1_1") (pintype "passive"))
      (node (ref "USB") (pin "1") (pinfunction "1_1") (pintype "passive"))
    )
    (net (code "151") (name "Net-(R41-Pad2)") (class "Default")
      (node (ref "R41") (pin "2") (pinfunction "2_2") (pintype "passive"))
      (node (ref "R42") (pin "1") (pinfunction "1_1") (pintype "passive"))
      (node (ref "R44") (pin "2") (pinfunction "2_2") (pintype "passive"))
    )
    (net (code "152") (name "Net-(R42-Pad2)") (class "Default")
      (node (ref "R42") (pin "2") (pinfunction "2_2") (pintype "passive"))
      (node (ref "REF2") (pin "3") (pinfunction "3_3") (pintype "passive"))
    )
    (net (code "153") (name "Net-(R45-Pad2)") (class "Default")
      (node (ref "R45") (pin "2") (pinfunction "2_2") (pintype "passive"))
      (node (ref "R46") (pin "1") (pinfunction "1_1") (pintype "passive"))
      (node (ref "R62") (pin "2") (pinfunction "2_2") (pintype "passive"))
    )
    (net (code "154") (name "Net-(R47-Pad2)") (class "Default")
      (node (ref "R47") (pin "2") (pinfunction "2_2") (pintype "passive"))
      (node (ref "R48") (pin "1") (pinfunction "1_1") (pintype "passive"))
      (node (ref "R77") (pin "2") (pinfunction "2_2") (pintype "passive"))
    )
    (net (code "155") (name "PH115") (class "Default")
      (node (ref "IC15") (pin "1") (pinfunction "OUT_1") (pintype "output"))
      (node (ref "IC16") (pin "1") (pinfunction "I0_1") (pintype "input"))
      (node (ref "IC16") (pin "12") (pinfunction "I0_12") (pintype "input"))
      (node (ref "IC17") (pin "11") (pinfunction "B_11") (pintype "input"))
      (node (ref "R59") (pin "1") (pinfunction "1_1") (pintype "passive"))
      (node (ref "R67") (pin "1") (pinfunction "1_1") (pintype "passive"))
    )
    (net (code "156") (name "PHCOS") (class "Default")
      (node (ref "IC16") (pin "9") (pinfunction "I1_9") (pintype "input"))
      (node (ref "IC18") (pin "1") (pinfunction "OUT_1") (pintype "output"))
      (node (ref "R82") (pin "1") (pinfunction "1_1") (pintype "passive"))
      (node (ref "R83") (pin "1") (pinfunction "1_1") (pintype "passive"))
    )
    (net (code "157") (name "PHHDG") (class "Default")
      (node (ref "IC15") (pin "7") (pinfunction "OUT_7") (pintype "output"))
      (node (ref "IC16") (pin "13") (pinfunction "I1_13") (pintype "input"))
      (node (ref "R65") (pin "1") (pinfunction "1_1") (pintype "passive"))
      (node (ref "R66") (pin "1") (pinfunction "1_1") (pintype "passive"))
    )
    (net (code "158") (name "PHSIN") (class "Default")
      (node (ref "IC16") (pin "2") (pinfunction "I1_2") (pintype "input"))
      (node (ref "IC16") (pin "8") (pinfunction "I0_8") (pintype "input"))
      (node (ref "IC18") (pin "7") (pinfunction "OUT_7") (pintype "output"))
      (node (ref "R84") (pin "1") (pinfunction "1_1") (pintype "passive"))
      (node (ref "R85") (pin "1") (pinfunction "1_1") (pintype "passive"))
    )
    (net (code "159") (name "PWRON") (class "Default")
      (node (ref "IC1") (pin "22") (pinfunction "RD3/SPP3_22") (pintype "bidirectional"))
      (node (ref "IC17") (pin "10") (pinfunction "Q_10") (pintype "output"))
    )
    (net (code "160") (name "REF115") (class "Default")
      (node (ref "R39") (pin "2") (pinfunction "2_2") (pintype "passive"))
      (node (ref "REF2") (pin "1") (pinfunction "1_1") (pintype "passive"))
    )
    (net (code "161") (name "SIG115") (class "Default")
      (node (ref "IC14") (pin "13") (pinfunction "-IN_13") (pintype "input"))
      (node (ref "IC14") (pin "14") (pinfunction "OUT_14") (pintype "output"))
      (node (ref "R29") (pin "2") (pinfunction "2_2") (pintype "passive"))
      (node (ref "R30") (pin "2") (pinfunction "2_2") (pintype "passive"))
      (node (ref "R50") (pin "2") (pinfunction "2_2") (pintype "passive"))
    )
    (net (code "162") (name "SPARE24") (class "Default")
      (node (ref "IC1") (pin "40") (pinfunction "RB7/BKI3/PGD_40") (pintype "bidirectional"))
      (node (ref "IC6") (pin "2") (pinfunction "1A_2") (pintype "input"))
    )
    (net (code "163") (name "SPI_CLK") (class "Default")
      (node (ref "IC1") (pin "34") (pinfunction "RB1/AN10/INT1/SCK/SCL_34") (pintype "bidirectional"))
      (node (ref "IC2") (pin "3") (pinfunction "SCK_3") (pintype "input"))
      (node (ref "IC3") (pin "3") (pinfunction "SCK_3") (pintype "input"))
      (node (ref "IC4") (pin "3") (pinfunction "SCK_3") (pintype "input"))
    )
    (net (code "164") (name "SPI_DAT") (class "Default")
      (node (ref "IC1") (pin "26") (pinfunction "RC7/RX/DT/SDO_26") (pintype "bidirectional"))
      (node (ref "IC2") (pin "4") (pinfunction "SDI_4") (pintype "input"))
      (node (ref "IC3") (pin "4") (pinfunction "SDI_4") (pintype "input"))
      (node (ref "IC4") (pin "4") (pinfunction "SDI_4") (pintype "input"))
    )
    (net (code "165") (name "TO_FLAG") (class "Default")
      (node (ref "IC1") (pin "39") (pinfunction "RB6/KBI2/PGC_39") (pintype "bidirectional"))
      (node (ref "IC6") (pin "15") (pinfunction "4A_15") (pintype "input"))
    )
    (net (code "166") (name "USBDOA") (class "Default")
      (node (ref "IC1") (pin "7") (pinfunction "RA5/AN4/~{SS}/HLVDIN/C2OUT_7") (pintype "bidirectional"))
      (node (ref "R2") (pin "1") (pinfunction "1_1") (pintype "passive"))
      (node (ref "U/D") (pin "2") (pinfunction "2_2") (pintype "passive"))
    )
    (net (code "167") (name "USB_DM") (class "Default")
      (node (ref "IC1") (pin "23") (pinfunction "RC4/D-/VM_23") (pintype "bidirectional"))
      (node (ref "USB") (pin "2") (pinfunction "2_2") (pintype "passive"))
    )
    (net (code "168") (name "USB_DP") (class "Default")
      (node (ref "IC1") (pin "24") (pinfunction "RC5/D+/VP_24") (pintype "bidirectional"))
      (node (ref "USB") (pin "3") (pinfunction "3_3") (pintype "passive"))
    )
    (net (code "169") (name "VIN") (class "Default")
      (node (ref "IC6") (pin "8") (pinfunction "VCC2_8") (pintype "power_in"))
      (node (ref "V+") (pin "2") (pinfunction "2_2") (pintype "passive"))
    )
    (net (code "170") (name "unconnected-(IC9A-~{Q}-Pad2)") (class "Default")
      (node (ref "IC9") (pin "2") (pinfunction "~{Q}_2") (pintype "output"))
    )
    (net (code "171") (name "unconnected-(IC9B-~{Q}-Pad12)") (class "Default")
      (node (ref "IC9") (pin "12") (pinfunction "~{Q}_12") (pintype "output"))
    )
    (net (code "172") (name "unconnected-(IC10A-~{Q}-Pad2)") (class "Default")
      (node (ref "IC10") (pin "2") (pinfunction "~{Q}_2") (pintype "output"))
    )
    (net (code "173") (name "unconnected-(IC10B-Q-Pad13)") (class "Default")
      (node (ref "IC10") (pin "13") (pinfunction "Q_13") (pintype "output"))
    )
    (net (code "174") (name "unconnected-(IC10B-~{Q}-Pad12)") (class "Default")
      (node (ref "IC10") (pin "12") (pinfunction "~{Q}_12") (pintype "output"))
    )
    (net (code "175") (name "unconnected-(IC11A-Q-Pad6)") (class "Default")
      (node (ref "IC11") (pin "6") (pinfunction "Q_6") (pintype "output"))
    )
    (net (code "176") (name "unconnected-(IC11B-Q-Pad10)") (class "Default")
      (node (ref "IC11") (pin "10") (pinfunction "Q_10") (pintype "output"))
    )
    (net (code "177") (name "unconnected-(IC12D-OUT-Pad13)") (class "Default")
      (node (ref "IC12") (pin "13") (pinfunction "OUT_13") (pintype "output"))
    )
    (net (code "178") (name "unconnected-(IC12E-MODE-Pad1)") (class "Default")
      (node (ref "IC12") (pin "1") (pinfunction "MODE_1") (pintype "input"))
    )
    (net (code "179") (name "unconnected-(IC16B-O-Pad4)") (class "Default")
      (node (ref "IC16") (pin "4") (pinfunction "O_4") (pintype "output"))
    )
    (net (code "180") (name "unconnected-(IC17A-Q-Pad6)") (class "Default")
      (node (ref "IC17") (pin "6") (pinfunction "Q_6") (pintype "output"))
    )
    (net (code "181") (name "unconnected-(IC17B-~{Q}-Pad9)") (class "Default")
      (node (ref "IC17") (pin "9") (pinfunction "~{Q}_9") (pintype "output"))
    )
  )
)
